# homeboard17.net
KiCad netlist of a schematic drawn in EAGLE
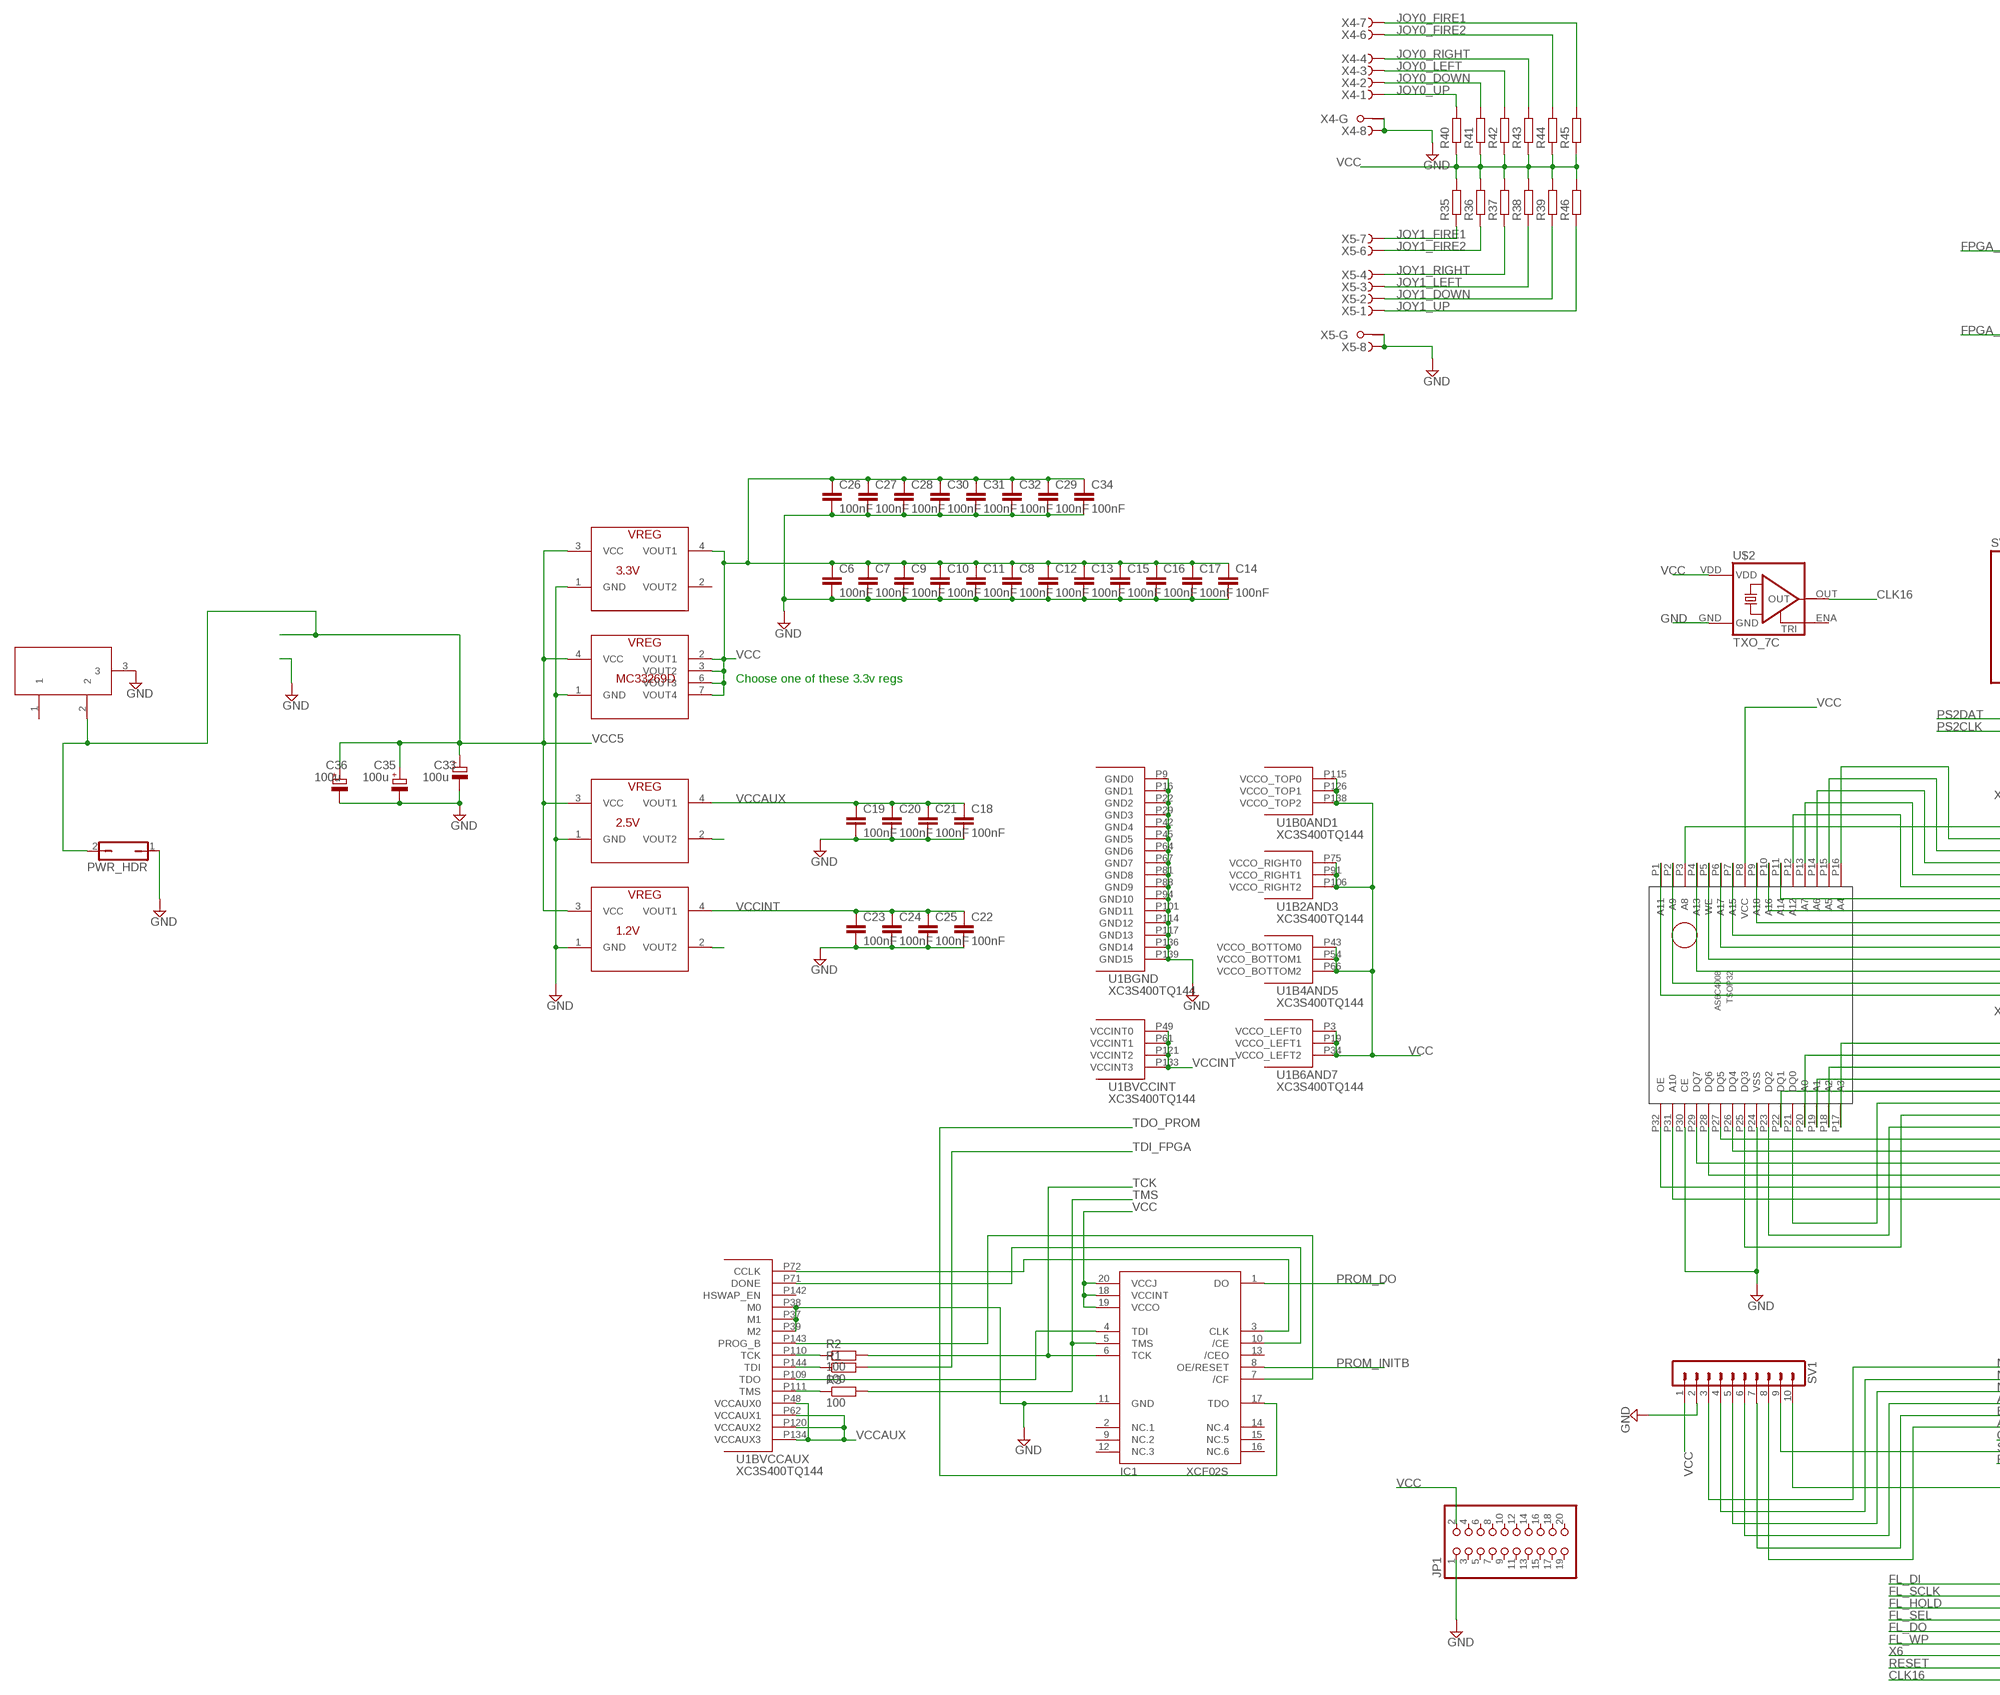
[diagram p0: schematic, sheet 1, part 1 of 3]
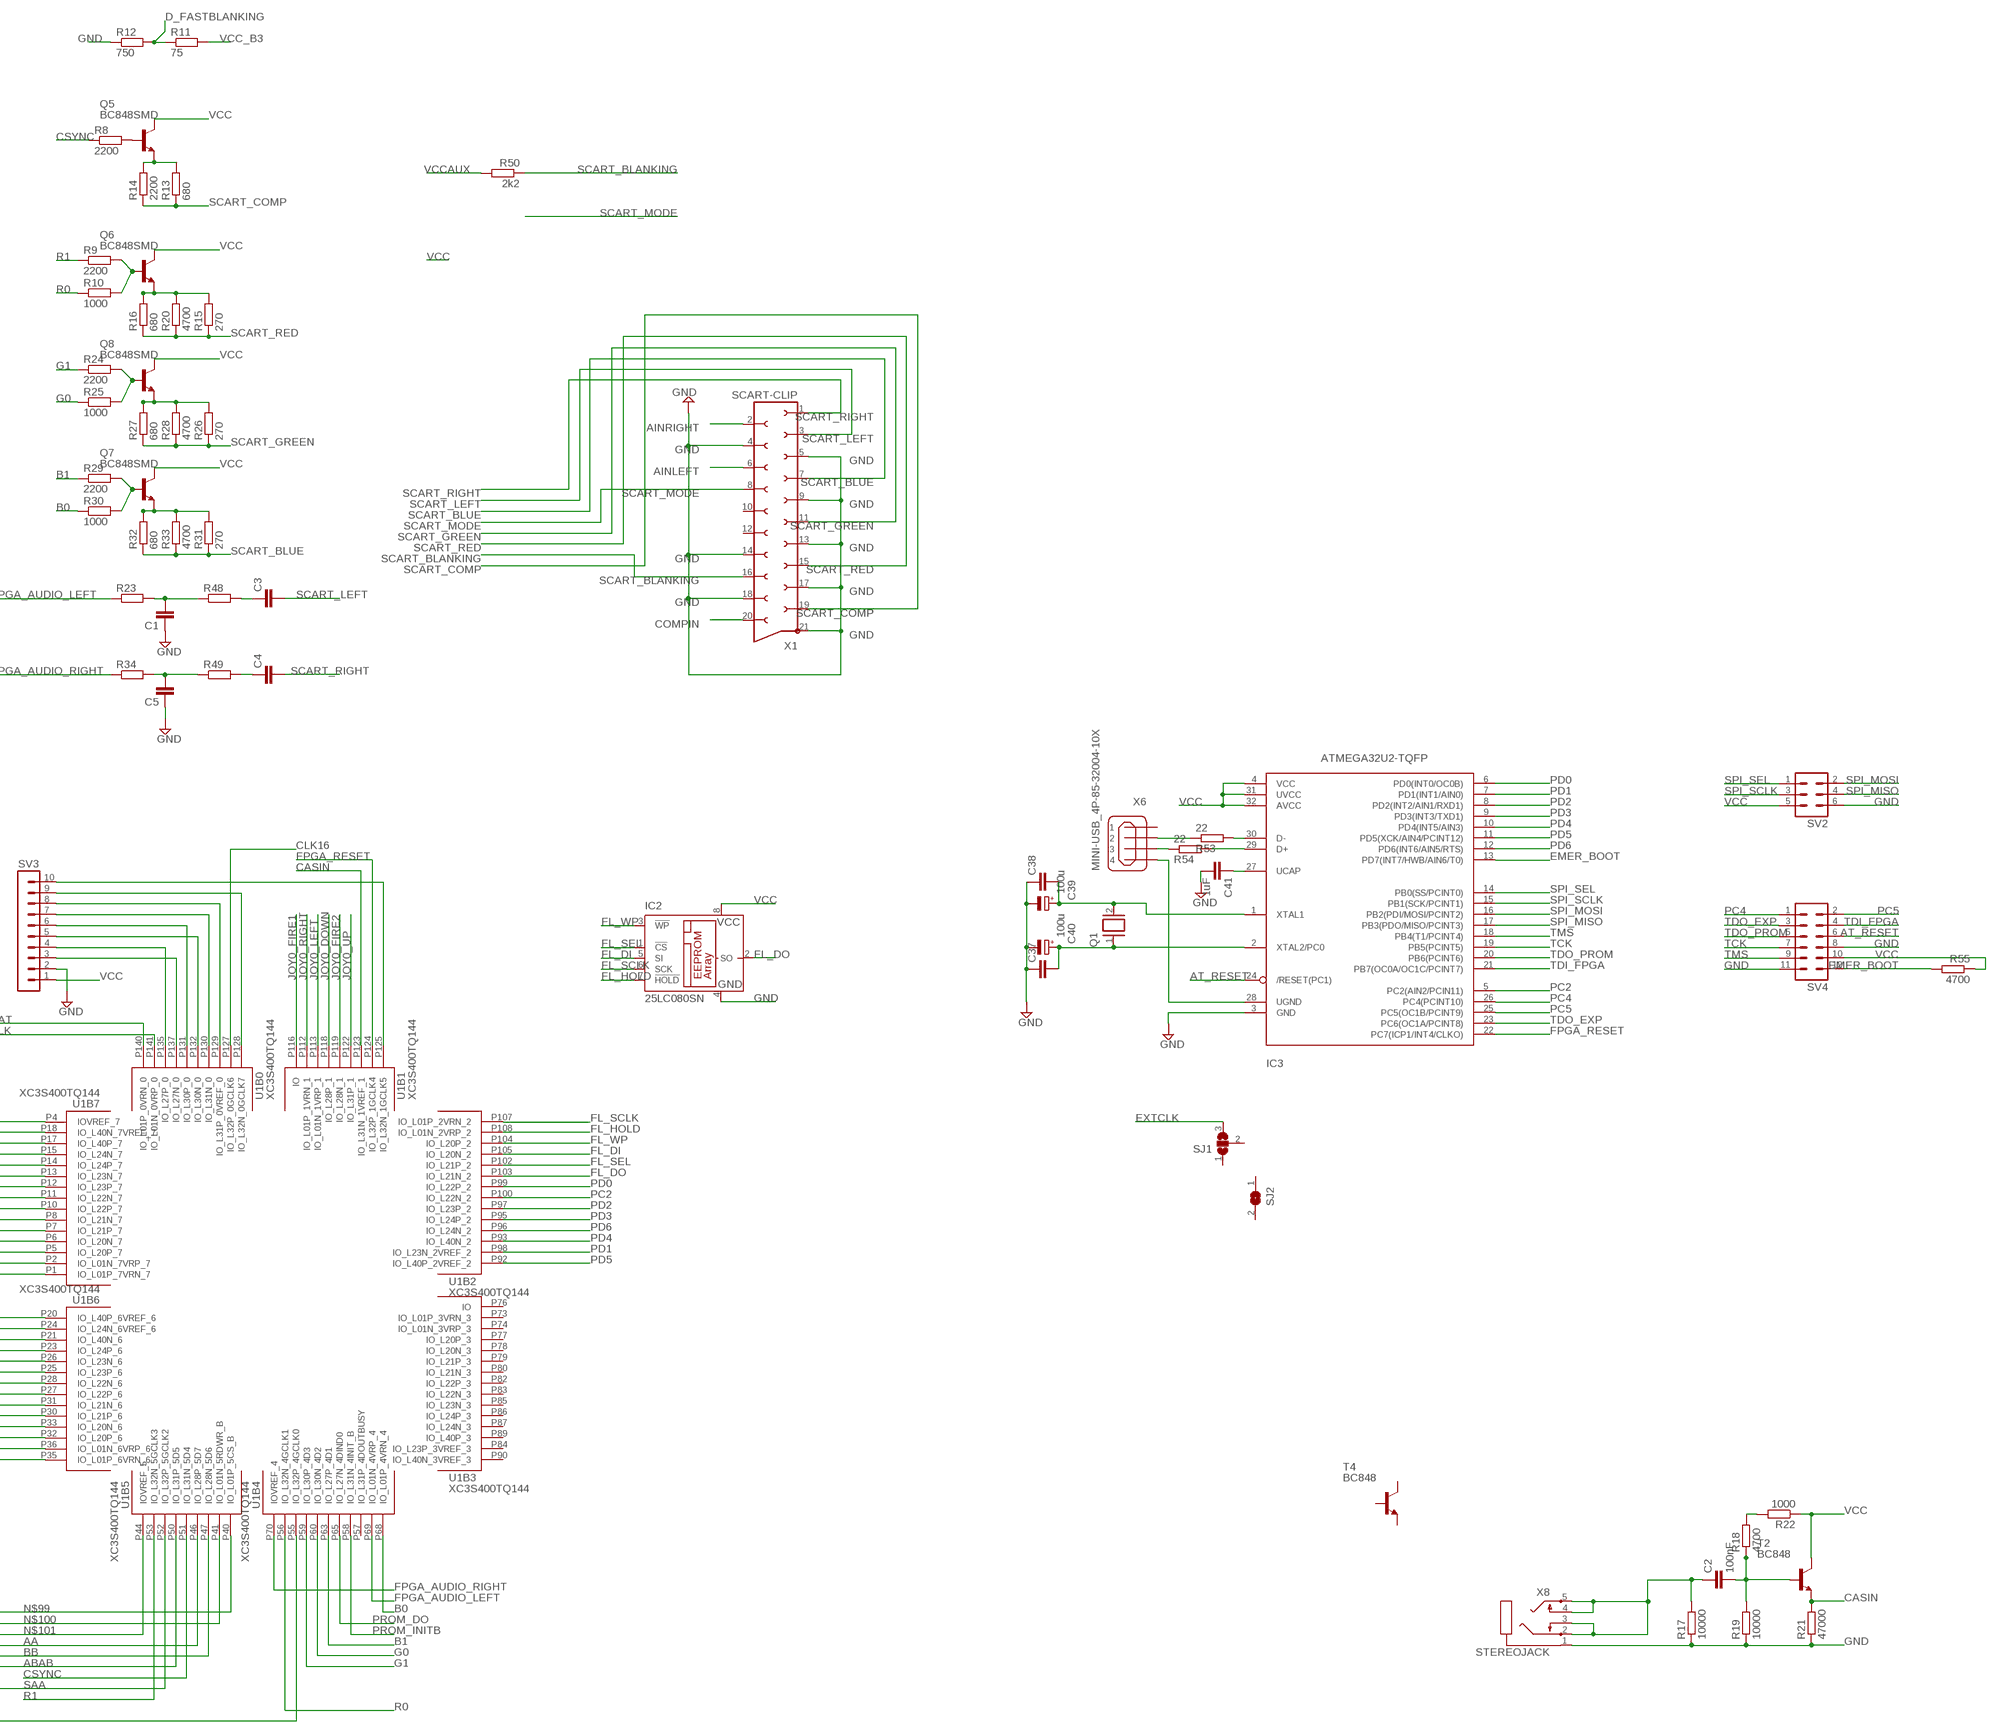
[diagram p1: schematic, sheet 1, part 2 of 3]
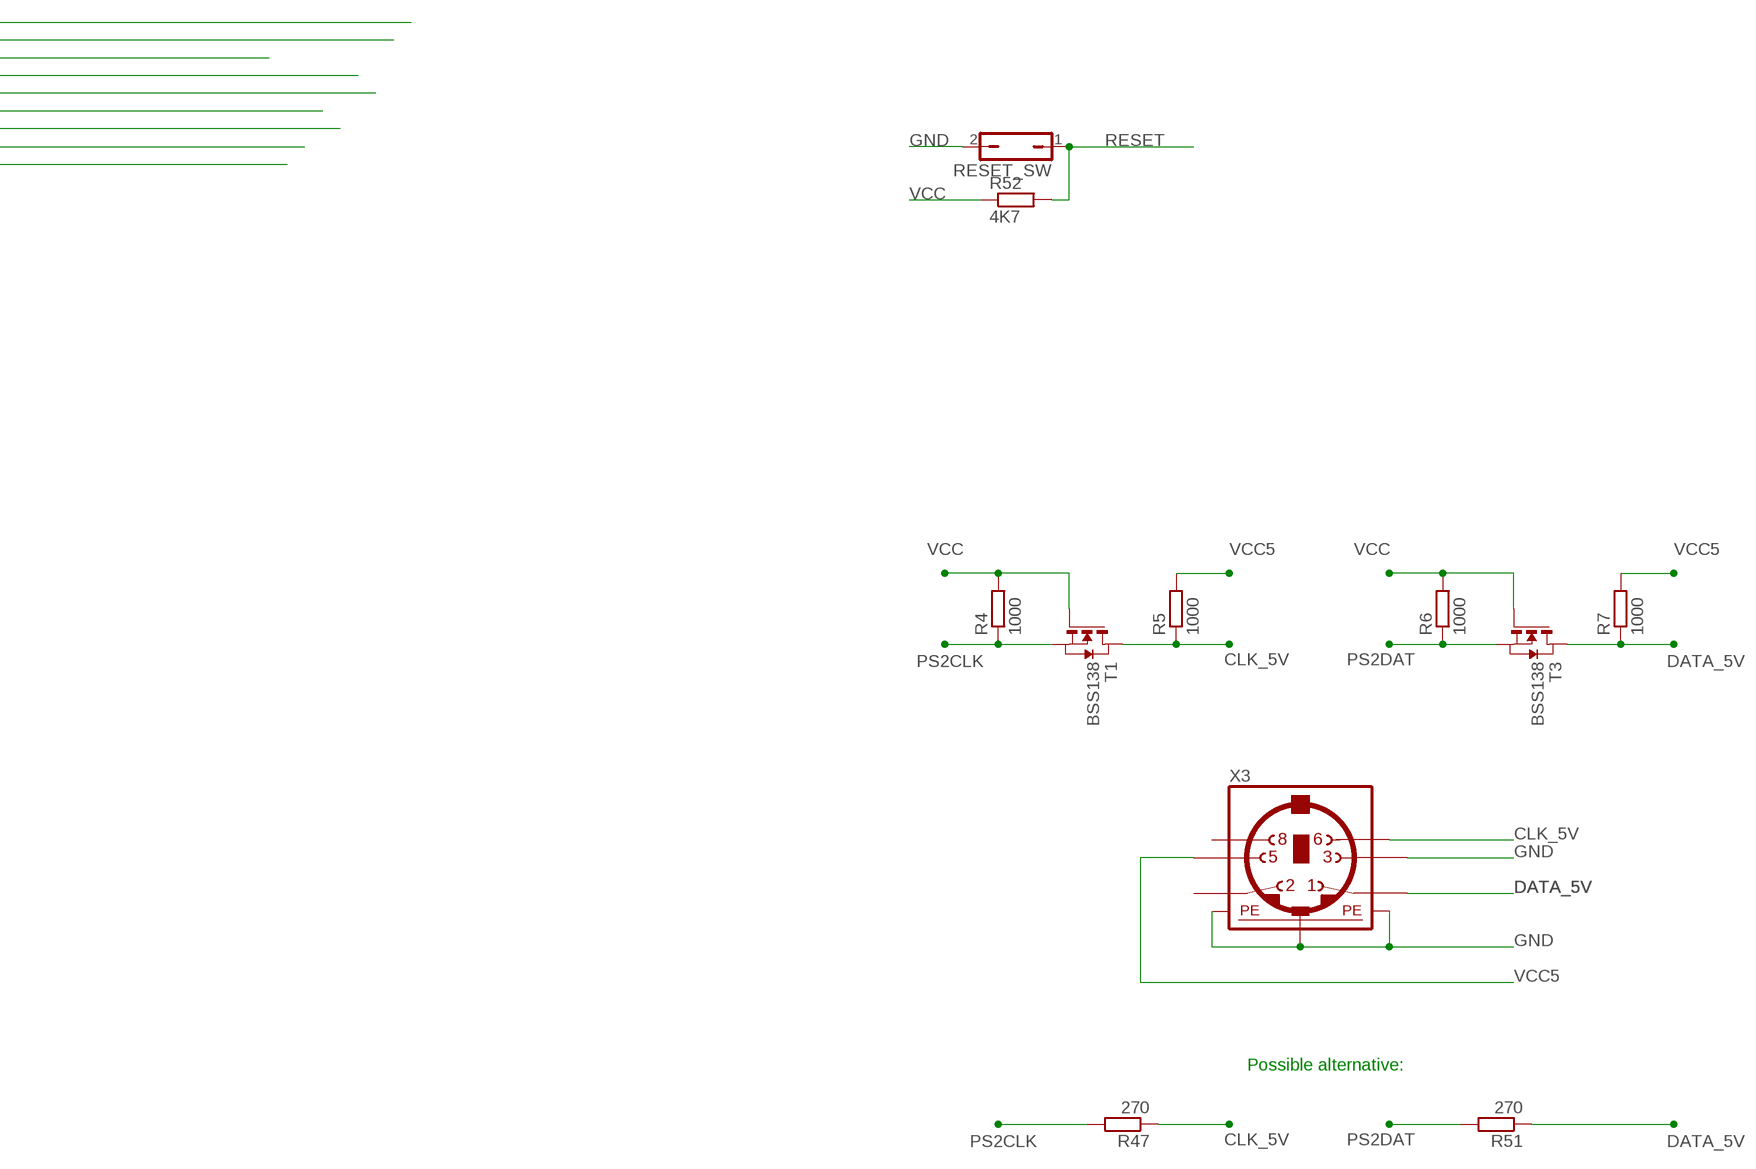
[diagram p2: schematic, sheet 1, part 3 of 3]

(export (version "E")
  (design (tool "Eeschema 10.0.6"))
  (components
    (comp (ref "C1")
      (value "C-EUC0603")
      (footprint "eagle-import:C0603")
      (libsource (lib "eagle-import") (part "resistor_C-EUC0603"))
    )
    (comp (ref "C2")
      (value "100nF")
      (footprint "eagle-import:C0603")
      (libsource (lib "eagle-import") (part "resistor_C-EUC0603"))
    )
    (comp (ref "C3")
      (value "C-EUC0603")
      (footprint "eagle-import:C0603")
      (libsource (lib "eagle-import") (part "resistor_C-EUC0603"))
    )
    (comp (ref "C4")
      (value "C-EUC0603")
      (footprint "eagle-import:C0603")
      (libsource (lib "eagle-import") (part "resistor_C-EUC0603"))
    )
    (comp (ref "C5")
      (value "C-EUC0603")
      (footprint "eagle-import:C0603")
      (libsource (lib "eagle-import") (part "resistor_C-EUC0603"))
    )
    (comp (ref "C6")
      (value "100nF")
      (footprint "eagle-import:C0603")
      (libsource (lib "eagle-import") (part "C-EUC0603"))
    )
    (comp (ref "C7")
      (value "100nF")
      (footprint "eagle-import:C0603")
      (libsource (lib "eagle-import") (part "C-EUC0603"))
    )
    (comp (ref "C8")
      (value "100nF")
      (footprint "eagle-import:C0603")
      (libsource (lib "eagle-import") (part "C-EUC0603"))
    )
    (comp (ref "C9")
      (value "100nF")
      (footprint "eagle-import:C0603")
      (libsource (lib "eagle-import") (part "C-EUC0603"))
    )
    (comp (ref "C10")
      (value "100nF")
      (footprint "eagle-import:C0603")
      (libsource (lib "eagle-import") (part "C-EUC0603"))
    )
    (comp (ref "C11")
      (value "100nF")
      (footprint "eagle-import:C0603")
      (libsource (lib "eagle-import") (part "C-EUC0603"))
    )
    (comp (ref "C12")
      (value "100nF")
      (footprint "eagle-import:C0603")
      (libsource (lib "eagle-import") (part "C-EUC0603"))
    )
    (comp (ref "C13")
      (value "100nF")
      (footprint "eagle-import:C0603")
      (libsource (lib "eagle-import") (part "C-EUC0603"))
    )
    (comp (ref "C14")
      (value "100nF")
      (footprint "eagle-import:C0603")
      (libsource (lib "eagle-import") (part "C-EUC0603"))
    )
    (comp (ref "C15")
      (value "100nF")
      (footprint "eagle-import:C0603")
      (libsource (lib "eagle-import") (part "C-EUC0603"))
    )
    (comp (ref "C16")
      (value "100nF")
      (footprint "eagle-import:C0603")
      (libsource (lib "eagle-import") (part "C-EUC0603"))
    )
    (comp (ref "C17")
      (value "100nF")
      (footprint "eagle-import:C0603")
      (libsource (lib "eagle-import") (part "C-EUC0603"))
    )
    (comp (ref "C18")
      (value "100nF")
      (footprint "eagle-import:C0603")
      (libsource (lib "eagle-import") (part "C-EUC0603"))
    )
    (comp (ref "C19")
      (value "100nF")
      (footprint "eagle-import:C0603")
      (libsource (lib "eagle-import") (part "C-EUC0603"))
    )
    (comp (ref "C20")
      (value "100nF")
      (footprint "eagle-import:C0603")
      (libsource (lib "eagle-import") (part "C-EUC0603"))
    )
    (comp (ref "C21")
      (value "100nF")
      (footprint "eagle-import:C0603")
      (libsource (lib "eagle-import") (part "C-EUC0603"))
    )
    (comp (ref "C22")
      (value "100nF")
      (footprint "eagle-import:C0603")
      (libsource (lib "eagle-import") (part "C-EUC0603"))
    )
    (comp (ref "C23")
      (value "100nF")
      (footprint "eagle-import:C0603")
      (libsource (lib "eagle-import") (part "C-EUC0603"))
    )
    (comp (ref "C24")
      (value "100nF")
      (footprint "eagle-import:C0603")
      (libsource (lib "eagle-import") (part "C-EUC0603"))
    )
    (comp (ref "C25")
      (value "100nF")
      (footprint "eagle-import:C0603")
      (libsource (lib "eagle-import") (part "C-EUC0603"))
    )
    (comp (ref "C26")
      (value "100nF")
      (footprint "eagle-import:C0603")
      (libsource (lib "eagle-import") (part "C-EUC0603"))
    )
    (comp (ref "C27")
      (value "100nF")
      (footprint "eagle-import:C0603")
      (libsource (lib "eagle-import") (part "C-EUC0603"))
    )
    (comp (ref "C28")
      (value "100nF")
      (footprint "eagle-import:C0603")
      (libsource (lib "eagle-import") (part "C-EUC0603"))
    )
    (comp (ref "C29")
      (value "100nF")
      (footprint "eagle-import:C0603")
      (libsource (lib "eagle-import") (part "C-EUC0603"))
    )
    (comp (ref "C30")
      (value "100nF")
      (footprint "eagle-import:C0603")
      (libsource (lib "eagle-import") (part "C-EUC0603"))
    )
    (comp (ref "C31")
      (value "100nF")
      (footprint "eagle-import:C0603")
      (libsource (lib "eagle-import") (part "C-EUC0603"))
    )
    (comp (ref "C32")
      (value "100nF")
      (footprint "eagle-import:C0603")
      (libsource (lib "eagle-import") (part "C-EUC0603"))
    )
    (comp (ref "C33")
      (value "100u")
      (footprint "eagle-import:PANASONIC_D")
      (libsource (lib "eagle-import") (part "CPOL-EUD"))
    )
    (comp (ref "C34")
      (value "100nF")
      (footprint "eagle-import:C0603")
      (libsource (lib "eagle-import") (part "C-EUC0603"))
    )
    (comp (ref "C35")
      (value "100u")
      (footprint "eagle-import:PANASONIC_D")
      (libsource (lib "eagle-import") (part "CPOL-EUD"))
    )
    (comp (ref "C36")
      (value "100u")
      (footprint "eagle-import:PANASONIC_D")
      (libsource (lib "eagle-import") (part "CPOL-EUD"))
    )
    (comp (ref "C37")
      (value "C-EUC0805")
      (footprint "eagle-import:C0805")
      (libsource (lib "eagle-import") (part "C-EUC0805"))
    )
    (comp (ref "C38")
      (value "C-EUC0805")
      (footprint "eagle-import:C0805")
      (libsource (lib "eagle-import") (part "C-EUC0805"))
    )
    (comp (ref "C39")
      (value "100u")
      (footprint "eagle-import:PANASONIC_D")
      (libsource (lib "eagle-import") (part "CPOL-EUD"))
    )
    (comp (ref "C40")
      (value "100u")
      (footprint "eagle-import:PANASONIC_D")
      (libsource (lib "eagle-import") (part "CPOL-EUD"))
    )
    (comp (ref "C41")
      (value "1uF")
      (footprint "eagle-import:C0805")
      (libsource (lib "eagle-import") (part "C-EUC0805"))
    )
    (comp (ref "IC1")
      (value "XCF02S")
      (footprint "eagle-import:VO20")
      (libsource (lib "eagle-import") (part "XCF02S"))
    )
    (comp (ref "IC2")
      (value "25LC080SN")
      (footprint "eagle-import:SO-08")
      (fields (field (name "MF") "MICROCHIP") (field (name "MPN") "25LC080/SN"))
      (libsource (lib "eagle-import") (part "25SNLC080"))
    )
    (comp (ref "IC3")
      (value "ATMEGA32U2-TQFP")
      (footprint "eagle-import:TQFP32-08")
      (libsource (lib "eagle-import") (part "ATMEGA32U2-TQFP"))
    )
    (comp (ref "JP1")
      (value "PINHD-2X10")
      (footprint "eagle-import:2X10")
      (libsource (lib "eagle-import") (part "PINHD-2X10"))
    )
    (comp (ref "PWR_HDR")
      (value "JP1Q")
      (footprint "eagle-import:JP1")
      (libsource (lib "eagle-import") (part "JP1Q"))
    )
    (comp (ref "Q1")
      (value "XTAL/S")
      (footprint "eagle-import:QS")
      (libsource (lib "eagle-import") (part "XTAL/S"))
    )
    (comp (ref "Q5")
      (value "BC848SMD")
      (footprint "eagle-import:SOT23")
      (libsource (lib "eagle-import") (part "BC848SMD"))
    )
    (comp (ref "Q6")
      (value "BC848SMD")
      (footprint "eagle-import:SOT23")
      (libsource (lib "eagle-import") (part "BC848SMD"))
    )
    (comp (ref "Q7")
      (value "BC848SMD")
      (footprint "eagle-import:SOT23")
      (libsource (lib "eagle-import") (part "BC848SMD"))
    )
    (comp (ref "Q8")
      (value "BC848SMD")
      (footprint "eagle-import:SOT23")
      (libsource (lib "eagle-import") (part "BC848SMD"))
    )
    (comp (ref "R1")
      (value "100")
      (footprint "eagle-import:R0805")
      (libsource (lib "eagle-import") (part "R-EU_R0805"))
    )
    (comp (ref "R2")
      (value "100")
      (footprint "eagle-import:R0805")
      (libsource (lib "eagle-import") (part "R-EU_R0805"))
    )
    (comp (ref "R3")
      (value "100")
      (footprint "eagle-import:R0805")
      (libsource (lib "eagle-import") (part "R-EU_R0805"))
    )
    (comp (ref "R4")
      (value "1000")
      (footprint "eagle-import:R0805")
      (libsource (lib "eagle-import") (part "R-EU_R0805"))
    )
    (comp (ref "R5")
      (value "1000")
      (footprint "eagle-import:R0805")
      (libsource (lib "eagle-import") (part "R-EU_R0805"))
    )
    (comp (ref "R6")
      (value "1000")
      (footprint "eagle-import:R0805")
      (libsource (lib "eagle-import") (part "R-EU_R0805"))
    )
    (comp (ref "R7")
      (value "1000")
      (footprint "eagle-import:R0805")
      (libsource (lib "eagle-import") (part "R-EU_R0805"))
    )
    (comp (ref "R8")
      (value "2200")
      (footprint "eagle-import:R0805")
      (libsource (lib "eagle-import") (part "R-EU_R0805"))
    )
    (comp (ref "R9")
      (value "2200")
      (footprint "eagle-import:R0805")
      (libsource (lib "eagle-import") (part "R-EU_R0805"))
    )
    (comp (ref "R10")
      (value "1000")
      (footprint "eagle-import:R0805")
      (libsource (lib "eagle-import") (part "R-EU_R0805"))
    )
    (comp (ref "R11")
      (value "75")
      (footprint "eagle-import:R0805")
      (libsource (lib "eagle-import") (part "R-EU_R0805"))
    )
    (comp (ref "R12")
      (value "750")
      (footprint "eagle-import:R0805")
      (libsource (lib "eagle-import") (part "R-EU_R0805"))
    )
    (comp (ref "R13")
      (value "680")
      (footprint "eagle-import:R0805")
      (libsource (lib "eagle-import") (part "R-EU_R0805"))
    )
    (comp (ref "R14")
      (value "2200")
      (footprint "eagle-import:R0805")
      (libsource (lib "eagle-import") (part "R-EU_R0805"))
    )
    (comp (ref "R15")
      (value "270")
      (footprint "eagle-import:R0805")
      (libsource (lib "eagle-import") (part "R-EU_R0805"))
    )
    (comp (ref "R16")
      (value "680")
      (footprint "eagle-import:R0805")
      (libsource (lib "eagle-import") (part "R-EU_R0805"))
    )
    (comp (ref "R17")
      (value "10000")
      (footprint "eagle-import:R0805")
      (libsource (lib "eagle-import") (part "R-EU_R0805"))
    )
    (comp (ref "R18")
      (value "4700")
      (footprint "eagle-import:R0805")
      (libsource (lib "eagle-import") (part "R-EU_R0805"))
    )
    (comp (ref "R19")
      (value "10000")
      (footprint "eagle-import:R0805")
      (libsource (lib "eagle-import") (part "R-EU_R0805"))
    )
    (comp (ref "R20")
      (value "4700")
      (footprint "eagle-import:R0805")
      (libsource (lib "eagle-import") (part "R-EU_R0805"))
    )
    (comp (ref "R21")
      (value "47000")
      (footprint "eagle-import:R0805")
      (libsource (lib "eagle-import") (part "R-EU_R0805"))
    )
    (comp (ref "R22")
      (value "1000")
      (footprint "eagle-import:R0805")
      (libsource (lib "eagle-import") (part "R-EU_R0805"))
    )
    (comp (ref "R23")
      (value "R-EU_M0805")
      (footprint "eagle-import:M0805")
      (libsource (lib "eagle-import") (part "resistor_R-EU_M0805"))
    )
    (comp (ref "R24")
      (value "2200")
      (footprint "eagle-import:R0805")
      (libsource (lib "eagle-import") (part "R-EU_R0805"))
    )
    (comp (ref "R25")
      (value "1000")
      (footprint "eagle-import:R0805")
      (libsource (lib "eagle-import") (part "R-EU_R0805"))
    )
    (comp (ref "R26")
      (value "270")
      (footprint "eagle-import:R0805")
      (libsource (lib "eagle-import") (part "R-EU_R0805"))
    )
    (comp (ref "R27")
      (value "680")
      (footprint "eagle-import:R0805")
      (libsource (lib "eagle-import") (part "R-EU_R0805"))
    )
    (comp (ref "R28")
      (value "4700")
      (footprint "eagle-import:R0805")
      (libsource (lib "eagle-import") (part "R-EU_R0805"))
    )
    (comp (ref "R29")
      (value "2200")
      (footprint "eagle-import:R0805")
      (libsource (lib "eagle-import") (part "R-EU_R0805"))
    )
    (comp (ref "R30")
      (value "1000")
      (footprint "eagle-import:R0805")
      (libsource (lib "eagle-import") (part "R-EU_R0805"))
    )
    (comp (ref "R31")
      (value "270")
      (footprint "eagle-import:R0805")
      (libsource (lib "eagle-import") (part "R-EU_R0805"))
    )
    (comp (ref "R32")
      (value "680")
      (footprint "eagle-import:R0805")
      (libsource (lib "eagle-import") (part "R-EU_R0805"))
    )
    (comp (ref "R33")
      (value "4700")
      (footprint "eagle-import:R0805")
      (libsource (lib "eagle-import") (part "R-EU_R0805"))
    )
    (comp (ref "R34")
      (value "R-EU_M0805")
      (footprint "eagle-import:M0805")
      (libsource (lib "eagle-import") (part "resistor_R-EU_M0805"))
    )
    (comp (ref "R35")
      (value "R-EU_M0805")
      (footprint "eagle-import:M0805")
      (libsource (lib "eagle-import") (part "resistor_R-EU_M0805"))
    )
    (comp (ref "R36")
      (value "R-EU_M0805")
      (footprint "eagle-import:M0805")
      (libsource (lib "eagle-import") (part "resistor_R-EU_M0805"))
    )
    (comp (ref "R37")
      (value "R-EU_M0805")
      (footprint "eagle-import:M0805")
      (libsource (lib "eagle-import") (part "resistor_R-EU_M0805"))
    )
    (comp (ref "R38")
      (value "R-EU_M0805")
      (footprint "eagle-import:M0805")
      (libsource (lib "eagle-import") (part "resistor_R-EU_M0805"))
    )
    (comp (ref "R39")
      (value "R-EU_M0805")
      (footprint "eagle-import:M0805")
      (libsource (lib "eagle-import") (part "resistor_R-EU_M0805"))
    )
    (comp (ref "R40")
      (value "R-EU_M0805")
      (footprint "eagle-import:M0805")
      (libsource (lib "eagle-import") (part "resistor_R-EU_M0805"))
    )
    (comp (ref "R41")
      (value "R-EU_M0805")
      (footprint "eagle-import:M0805")
      (libsource (lib "eagle-import") (part "resistor_R-EU_M0805"))
    )
    (comp (ref "R42")
      (value "R-EU_M0805")
      (footprint "eagle-import:M0805")
      (libsource (lib "eagle-import") (part "resistor_R-EU_M0805"))
    )
    (comp (ref "R43")
      (value "R-EU_M0805")
      (footprint "eagle-import:M0805")
      (libsource (lib "eagle-import") (part "resistor_R-EU_M0805"))
    )
    (comp (ref "R44")
      (value "R-EU_M0805")
      (footprint "eagle-import:M0805")
      (libsource (lib "eagle-import") (part "resistor_R-EU_M0805"))
    )
    (comp (ref "R45")
      (value "R-EU_M0805")
      (footprint "eagle-import:M0805")
      (libsource (lib "eagle-import") (part "resistor_R-EU_M0805"))
    )
    (comp (ref "R46")
      (value "R-EU_M0805")
      (footprint "eagle-import:M0805")
      (libsource (lib "eagle-import") (part "resistor_R-EU_M0805"))
    )
    (comp (ref "R47")
      (value "270")
      (footprint "eagle-import:R0805")
      (libsource (lib "eagle-import") (part "R-EU_R0805"))
    )
    (comp (ref "R48")
      (value "R-EU_M0805")
      (footprint "eagle-import:M0805")
      (libsource (lib "eagle-import") (part "resistor_R-EU_M0805"))
    )
    (comp (ref "R49")
      (value "R-EU_M0805")
      (footprint "eagle-import:M0805")
      (libsource (lib "eagle-import") (part "resistor_R-EU_M0805"))
    )
    (comp (ref "R50")
      (value "2k2")
      (footprint "eagle-import:M0805")
      (libsource (lib "eagle-import") (part "resistor_R-EU_M0805"))
    )
    (comp (ref "R51")
      (value "270")
      (footprint "eagle-import:R0805")
      (libsource (lib "eagle-import") (part "R-EU_R0805"))
    )
    (comp (ref "R52")
      (value "4K7")
      (footprint "eagle-import:M0805")
      (libsource (lib "eagle-import") (part "resistor_R-EU_M0805"))
    )
    (comp (ref "R53")
      (value "22")
      (footprint "eagle-import:R0805")
      (libsource (lib "eagle-import") (part "R-EU_R0805"))
    )
    (comp (ref "R54")
      (value "22")
      (footprint "eagle-import:R0805")
      (libsource (lib "eagle-import") (part "R-EU_R0805"))
    )
    (comp (ref "R55")
      (value "4700")
      (footprint "eagle-import:R0805")
      (libsource (lib "eagle-import") (part "R-EU_R0805"))
    )
    (comp (ref "REG1.2")
      (value "1.2V")
      (footprint "eagle-import:SOT223")
      (libsource (lib "eagle-import") (part "NX1117"))
    )
    (comp (ref "REG2.5")
      (value "2.5V")
      (footprint "eagle-import:SOT223")
      (libsource (lib "eagle-import") (part "NX1117"))
    )
    (comp (ref "RESET_SW")
      (value "JP1Q")
      (footprint "eagle-import:JP1")
      (libsource (lib "eagle-import") (part "JP1Q"))
    )
    (comp (ref "SJ1")
      (value "SJ2W")
      (footprint "eagle-import:SJ_2")
      (libsource (lib "eagle-import") (part "SJ2W"))
    )
    (comp (ref "SJ2") (value "SJ") (footprint "eagle-import:SJ") (libsource (lib "eagle-import") (part "SJ")))
    (comp (ref "SV1")
      (value "MA10-1")
      (footprint "eagle-import:MA10-1")
      (fields (field (name "OC_FARNELL") "unknown") (field (name "OC_NEWARK") "unknown"))
      (libsource (lib "eagle-import") (part "MA10-1"))
    )
    (comp (ref "SV2")
      (value "MA03-2")
      (footprint "eagle-import:MA03-2")
      (libsource (lib "eagle-import") (part "MA03-2"))
    )
    (comp (ref "SV3")
      (value "MA10-1")
      (footprint "eagle-import:MA10-1")
      (libsource (lib "eagle-import") (part "MA10-1"))
    )
    (comp (ref "SV4")
      (value "MA06-2")
      (footprint "eagle-import:MA06-2")
      (libsource (lib "eagle-import") (part "MA06-2"))
    )
    (comp (ref "T1")
      (value "BSS138")
      (footprint "eagle-import:SOT-23")
      (libsource (lib "eagle-import") (part "NMOSSOT23"))
    )
    (comp (ref "T2")
      (value "BC848")
      (footprint "eagle-import:SOT23")
      (libsource (lib "eagle-import") (part "BC848"))
    )
    (comp (ref "T3")
      (value "BSS138")
      (footprint "eagle-import:SOT-23")
      (libsource (lib "eagle-import") (part "NMOSSOT23"))
    )
    (comp (ref "T4")
      (value "BC848")
      (footprint "eagle-import:SOT23")
      (libsource (lib "eagle-import") (part "BC848"))
    )
    (comp (ref "U$2")
      (value "TXO_7C")
      (footprint "eagle-import:OSC_7C")
      (libsource (lib "eagle-import") (part "TXO_7C"))
    )
    (comp (ref "U$4")
      (value "3.3V")
      (footprint "eagle-import:SOT223")
      (libsource (lib "eagle-import") (part "NX1117"))
    )
    (comp (ref "U$5")
      (value "MC33269D")
      (footprint "eagle-import:SO8")
      (libsource (lib "eagle-import") (part "MC33269D"))
    )
    (comp (ref "U$6")
      (value "AS6C4008")
      (footprint "eagle-import:TSOP32")
      (libsource (lib "eagle-import") (part "AS6C4008"))
    )
    (comp (ref "U1")
      (value "XC3S400TQ144")
      (footprint "eagle-import:TQ144")
      (libsource (lib "eagle-import") (part "XC3S400TQ144"))
    )
    (comp (ref "X1")
      (value "SCART-CLIP")
      (footprint "eagle-import:SCART-CLIP")
      (libsource (lib "eagle-import") (part "SCART-CLIP"))
    )
    (comp (ref "X3")
      (value "MINI_DIN_6")
      (footprint "eagle-import:M_DIN6")
      (libsource (lib "eagle-import") (part "MINI_DIN_6"))
    )
    (comp (ref "X4")
      (value "F09HPS")
      (footprint "eagle-import:F09HP")
      (libsource (lib "eagle-import") (part "F09HPS"))
    )
    (comp (ref "X5")
      (value "F09HPS")
      (footprint "eagle-import:F09HP")
      (libsource (lib "eagle-import") (part "F09HPS"))
    )
    (comp (ref "X6")
      (value "MINI-USB_4P-85-32004-10X")
      (footprint "eagle-import:85-32004-10X")
      (libsource (lib "eagle-import") (part "MINI-USB_4P-85-32004-10X"))
    )
    (comp (ref "X7")
      (value "DC21MMX")
      (footprint "eagle-import:DC-21MM")
      (libsource (lib "eagle-import") (part "DC21MMX"))
    )
    (comp (ref "X8")
      (value "STEREOJACK")
      (footprint "eagle-import:20-0137")
      (libsource (lib "eagle-import") (part "STEREOJACK"))
    )
  )
  (nets
    (net (code "1") (name "/1") (class "Default")
      (node (ref "X7") (pin "1") (pinfunction "1_1") (pintype "power_in"))
    )
    (net (code "2") (name "/AA") (class "Default")
      (node (ref "SV1") (pin "6") (pinfunction "6_6") (pintype "passive"))
      (node (ref "U1") (pin "P46") (pinfunction "IO_L28P_5D7_P46") (pintype "bidirectional"))
    )
    (net (code "3") (name "/ABAB") (class "Default")
      (node (ref "SV1") (pin "8") (pinfunction "8_8") (pintype "passive"))
      (node (ref "U1") (pin "P50") (pinfunction "IO_L31P_5D5_P50") (pintype "bidirectional"))
    )
    (net (code "4") (name "/AINLEFT") (class "Default")
      (node (ref "X1") (pin "6") (pinfunction "6_6") (pintype "passive"))
    )
    (net (code "5") (name "/AINRIGHT") (class "Default")
      (node (ref "X1") (pin "2") (pinfunction "2_2") (pintype "passive"))
    )
    (net (code "6") (name "/AT_RESET") (class "Default")
      (node (ref "IC3") (pin "24") (pinfunction "/RESET(PC1)_24") (pintype "bidirectional"))
      (node (ref "SV4") (pin "6") (pinfunction "6_6") (pintype "passive"))
    )
    (net (code "7") (name "/B0") (class "Default")
      (node (ref "R30") (pin "1") (pinfunction "1_1") (pintype "passive"))
      (node (ref "U1") (pin "P68") (pinfunction "IO_L01P_4VRN_4_P68") (pintype "bidirectional"))
    )
    (net (code "8") (name "/B1") (class "Default")
      (node (ref "R29") (pin "1") (pinfunction "1_1") (pintype "passive"))
      (node (ref "U1") (pin "P63") (pinfunction "IO_L27P_4D1_P63") (pintype "bidirectional"))
    )
    (net (code "9") (name "/BB") (class "Default")
      (node (ref "SV1") (pin "7") (pinfunction "7_7") (pintype "passive"))
      (node (ref "U1") (pin "P47") (pinfunction "IO_L28N_5D6_P47") (pintype "bidirectional"))
    )
    (net (code "10") (name "/CASIN") (class "Default")
      (node (ref "R21") (pin "2") (pinfunction "2_2") (pintype "passive"))
      (node (ref "T2") (pin "2") (pinfunction "E_2") (pintype "passive"))
      (node (ref "U1") (pin "P123") (pinfunction "IO_L31N_1VREF_1_P123") (pintype "bidirectional"))
    )
    (net (code "11") (name "/CLK16") (class "Default")
      (node (ref "U$2") (pin "OUT") (pinfunction "OUT_OUT") (pintype "output"))
      (node (ref "U1") (pin "P127") (pinfunction "IO_L32P_0GCLK6_P127") (pintype "bidirectional"))
    )
    (net (code "12") (name "/CLK_5V") (class "Default")
      (node (ref "R47") (pin "1") (pinfunction "1_1") (pintype "passive"))
      (node (ref "R5") (pin "1") (pinfunction "1_1") (pintype "passive"))
      (node (ref "T1") (pin "1") (pinfunction "D_1") (pintype "passive"))
      (node (ref "X3") (pin "6") (pinfunction "6_6") (pintype "passive"))
    )
    (net (code "13") (name "/COMPIN") (class "Default")
      (node (ref "X1") (pin "20") (pinfunction "20_20") (pintype "passive"))
    )
    (net (code "14") (name "/CSYNC") (class "Default")
      (node (ref "R8") (pin "1") (pinfunction "1_1") (pintype "passive"))
      (node (ref "U1") (pin "P51") (pinfunction "IO_L31N_5D4_P51") (pintype "bidirectional"))
    )
    (net (code "15") (name "/DATA_5V") (class "Default")
      (node (ref "R51") (pin "1") (pinfunction "1_1") (pintype "passive"))
      (node (ref "R7") (pin "1") (pinfunction "1_1") (pintype "passive"))
      (node (ref "T3") (pin "1") (pinfunction "D_1") (pintype "passive"))
      (node (ref "X3") (pin "1") (pinfunction "1_1") (pintype "passive"))
    )
    (net (code "16") (name "/D_FASTBLANKING") (class "Default")
      (node (ref "R11") (pin "1") (pinfunction "1_1") (pintype "passive"))
      (node (ref "R12") (pin "2") (pinfunction "2_2") (pintype "passive"))
    )
    (net (code "17") (name "/EMER_BOOT") (class "Default")
      (node (ref "IC3") (pin "13") (pinfunction "PD7(INT7/HWB/AIN6/T0)_13") (pintype "bidirectional"))
      (node (ref "R55") (pin "2") (pinfunction "2_2") (pintype "passive"))
      (node (ref "SV4") (pin "12") (pinfunction "12_12") (pintype "passive"))
    )
    (net (code "18") (name "/EXTCLK") (class "Default")
      (node (ref "SJ1") (pin "3") (pinfunction "3_3") (pintype "passive"))
    )
    (net (code "19") (name "/FL_DI") (class "Default")
      (node (ref "IC2") (pin "5") (pinfunction "SI_5") (pintype "input"))
      (node (ref "U1") (pin "P105") (pinfunction "IO_L20N_2_P105") (pintype "bidirectional"))
    )
    (net (code "20") (name "/FL_DO") (class "Default")
      (node (ref "IC2") (pin "2") (pinfunction "SO_2") (pintype "bidirectional"))
      (node (ref "U1") (pin "P103") (pinfunction "IO_L21N_2_P103") (pintype "bidirectional"))
    )
    (net (code "21") (name "/FL_HOLD") (class "Default")
      (node (ref "IC2") (pin "7") (pinfunction "~{HOLD}_7") (pintype "input"))
      (node (ref "U1") (pin "P108") (pinfunction "IO_L01N_2VRP_2_P108") (pintype "bidirectional"))
    )
    (net (code "22") (name "/FL_SCLK") (class "Default")
      (node (ref "IC2") (pin "6") (pinfunction "SCK_6") (pintype "input"))
      (node (ref "U1") (pin "P107") (pinfunction "IO_L01P_2VRN_2_P107") (pintype "bidirectional"))
    )
    (net (code "23") (name "/FL_SEL") (class "Default")
      (node (ref "IC2") (pin "1") (pinfunction "~{CS}_1") (pintype "input"))
      (node (ref "U1") (pin "P102") (pinfunction "IO_L21P_2_P102") (pintype "bidirectional"))
    )
    (net (code "24") (name "/FL_WP") (class "Default")
      (node (ref "IC2") (pin "3") (pinfunction "~{WP}_3") (pintype "input"))
      (node (ref "U1") (pin "P104") (pinfunction "IO_L20P_2_P104") (pintype "bidirectional"))
    )
    (net (code "25") (name "/FPGA_AUDIO_LEFT") (class "Default")
      (node (ref "R23") (pin "1") (pinfunction "1_1") (pintype "passive"))
      (node (ref "U1") (pin "P69") (pinfunction "IO_L01N_4VRP_4_P69") (pintype "bidirectional"))
    )
    (net (code "26") (name "/FPGA_AUDIO_RIGHT") (class "Default")
      (node (ref "R34") (pin "1") (pinfunction "1_1") (pintype "passive"))
      (node (ref "U1") (pin "P70") (pinfunction "IOVREF_4_P70") (pintype "bidirectional"))
    )
    (net (code "27") (name "/FPGA_RESET") (class "Default")
      (node (ref "IC3") (pin "22") (pinfunction "PC7(ICP1/INT4/CLKO)_22") (pintype "bidirectional"))
      (node (ref "U1") (pin "P124") (pinfunction "IO_L32P_1GCLK4_P124") (pintype "bidirectional"))
    )
    (net (code "28") (name "/G0") (class "Default")
      (node (ref "R25") (pin "1") (pinfunction "1_1") (pintype "passive"))
      (node (ref "U1") (pin "P60") (pinfunction "IO_L30N_4D2_P60") (pintype "bidirectional"))
    )
    (net (code "29") (name "/G1") (class "Default")
      (node (ref "R24") (pin "1") (pinfunction "1_1") (pintype "passive"))
      (node (ref "U1") (pin "P59") (pinfunction "IO_L30P_4D3_P59") (pintype "bidirectional"))
    )
    (net (code "30") (name "/JOY0_DOWN") (class "Default")
      (node (ref "R41") (pin "2") (pinfunction "2_2") (pintype "passive"))
      (node (ref "U1") (pin "P118") (pinfunction "IO_L28P_1_P118") (pintype "bidirectional"))
      (node (ref "X4") (pin "2") (pinfunction "F_2") (pintype "passive"))
    )
    (net (code "31") (name "/JOY0_FIRE1") (class "Default")
      (node (ref "R45") (pin "2") (pinfunction "2_2") (pintype "passive"))
      (node (ref "U1") (pin "P116") (pinfunction "IO_P116") (pintype "bidirectional"))
      (node (ref "X4") (pin "7") (pinfunction "F_7") (pintype "passive"))
    )
    (net (code "32") (name "/JOY0_FIRE2") (class "Default")
      (node (ref "R44") (pin "2") (pinfunction "2_2") (pintype "passive"))
      (node (ref "U1") (pin "P119") (pinfunction "IO_L28N_1_P119") (pintype "bidirectional"))
      (node (ref "X4") (pin "6") (pinfunction "F_6") (pintype "passive"))
    )
    (net (code "33") (name "/JOY0_LEFT") (class "Default")
      (node (ref "R42") (pin "2") (pinfunction "2_2") (pintype "passive"))
      (node (ref "U1") (pin "P113") (pinfunction "IO_L01N_1VRP_1_P113") (pintype "bidirectional"))
      (node (ref "X4") (pin "3") (pinfunction "F_3") (pintype "passive"))
    )
    (net (code "34") (name "/JOY0_RIGHT") (class "Default")
      (node (ref "R43") (pin "2") (pinfunction "2_2") (pintype "passive"))
      (node (ref "U1") (pin "P112") (pinfunction "IO_L01P_1VRN_1_P112") (pintype "bidirectional"))
      (node (ref "X4") (pin "4") (pinfunction "F_4") (pintype "passive"))
    )
    (net (code "35") (name "/JOY0_UP") (class "Default")
      (node (ref "R40") (pin "2") (pinfunction "2_2") (pintype "passive"))
      (node (ref "U1") (pin "P122") (pinfunction "IO_L31P_1_P122") (pintype "bidirectional"))
      (node (ref "X4") (pin "1") (pinfunction "F_1") (pintype "passive"))
    )
    (net (code "36") (name "/JOY1_DOWN") (class "Default")
      (node (ref "R39") (pin "1") (pinfunction "1_1") (pintype "passive"))
      (node (ref "X5") (pin "2") (pinfunction "F_2") (pintype "passive"))
    )
    (net (code "37") (name "/JOY1_FIRE1") (class "Default")
      (node (ref "R35") (pin "1") (pinfunction "1_1") (pintype "passive"))
      (node (ref "X5") (pin "7") (pinfunction "F_7") (pintype "passive"))
    )
    (net (code "38") (name "/JOY1_FIRE2") (class "Default")
      (node (ref "R36") (pin "1") (pinfunction "1_1") (pintype "passive"))
      (node (ref "X5") (pin "6") (pinfunction "F_6") (pintype "passive"))
    )
    (net (code "39") (name "/JOY1_LEFT") (class "Default")
      (node (ref "R38") (pin "1") (pinfunction "1_1") (pintype "passive"))
      (node (ref "X5") (pin "3") (pinfunction "F_3") (pintype "passive"))
    )
    (net (code "40") (name "/JOY1_RIGHT") (class "Default")
      (node (ref "R37") (pin "1") (pinfunction "1_1") (pintype "passive"))
      (node (ref "X5") (pin "4") (pinfunction "F_4") (pintype "passive"))
    )
    (net (code "41") (name "/JOY1_UP") (class "Default")
      (node (ref "R46") (pin "1") (pinfunction "1_1") (pintype "passive"))
      (node (ref "X5") (pin "1") (pinfunction "F_1") (pintype "passive"))
    )
    (net (code "42") (name "/N$99") (class "Default")
      (node (ref "SV1") (pin "3") (pinfunction "3_3") (pintype "passive"))
      (node (ref "U1") (pin "P40") (pinfunction "IO_L01P_5CS_B_P40") (pintype "bidirectional"))
    )
    (net (code "43") (name "/N$100") (class "Default")
      (node (ref "SV1") (pin "4") (pinfunction "4_4") (pintype "passive"))
      (node (ref "U1") (pin "P41") (pinfunction "IO_L01N_5RDWR_B_P41") (pintype "bidirectional"))
    )
    (net (code "44") (name "/N$101") (class "Default")
      (node (ref "SV1") (pin "5") (pinfunction "5_5") (pintype "passive"))
      (node (ref "U1") (pin "P44") (pinfunction "IOVREF_5_P44") (pintype "bidirectional"))
    )
    (net (code "45") (name "/PC2") (class "Default")
      (node (ref "IC3") (pin "5") (pinfunction "PC2(AIN2/PCIN11)_5") (pintype "bidirectional"))
      (node (ref "U1") (pin "P100") (pinfunction "IO_L22N_2_P100") (pintype "bidirectional"))
    )
    (net (code "46") (name "/PC4") (class "Default")
      (node (ref "IC3") (pin "26") (pinfunction "PC4(PCINT10)_26") (pintype "bidirectional"))
      (node (ref "SV4") (pin "1") (pinfunction "1_1") (pintype "passive"))
    )
    (net (code "47") (name "/PC5") (class "Default")
      (node (ref "IC3") (pin "25") (pinfunction "PC5(OC1B/PCINT9)_25") (pintype "bidirectional"))
      (node (ref "SV4") (pin "2") (pinfunction "2_2") (pintype "passive"))
    )
    (net (code "48") (name "/PD0") (class "Default")
      (node (ref "IC3") (pin "6") (pinfunction "PD0(INT0/OC0B)_6") (pintype "bidirectional"))
      (node (ref "U1") (pin "P99") (pinfunction "IO_L22P_2_P99") (pintype "bidirectional"))
    )
    (net (code "49") (name "/PD1") (class "Default")
      (node (ref "IC3") (pin "7") (pinfunction "PD1(INT1/AIN0)_7") (pintype "bidirectional"))
      (node (ref "U1") (pin "P98") (pinfunction "IO_L23N_2VREF_2_P98") (pintype "bidirectional"))
    )
    (net (code "50") (name "/PD2") (class "Default")
      (node (ref "IC3") (pin "8") (pinfunction "PD2(INT2/AIN1/RXD1)_8") (pintype "bidirectional"))
      (node (ref "U1") (pin "P97") (pinfunction "IO_L23P_2_P97") (pintype "bidirectional"))
    )
    (net (code "51") (name "/PD3") (class "Default")
      (node (ref "IC3") (pin "9") (pinfunction "PD3(INT3/TXD1)_9") (pintype "bidirectional"))
      (node (ref "U1") (pin "P95") (pinfunction "IO_L24P_2_P95") (pintype "bidirectional"))
    )
    (net (code "52") (name "/PD4") (class "Default")
      (node (ref "IC3") (pin "10") (pinfunction "PD4(INT5/AIN3)_10") (pintype "bidirectional"))
      (node (ref "U1") (pin "P93") (pinfunction "IO_L40N_2_P93") (pintype "bidirectional"))
    )
    (net (code "53") (name "/PD5") (class "Default")
      (node (ref "IC3") (pin "11") (pinfunction "PD5(XCK/AIN4/PCINT12)_11") (pintype "bidirectional"))
      (node (ref "U1") (pin "P92") (pinfunction "IO_L40P_2VREF_2_P92") (pintype "bidirectional"))
    )
    (net (code "54") (name "/PD6") (class "Default")
      (node (ref "IC3") (pin "12") (pinfunction "PD6(INT6/AIN5/RTS)_12") (pintype "bidirectional"))
      (node (ref "U1") (pin "P96") (pinfunction "IO_L24N_2_P96") (pintype "bidirectional"))
    )
    (net (code "55") (name "/PROM_DO") (class "Default")
      (node (ref "IC1") (pin "1") (pinfunction "DO_1") (pintype "bidirectional"))
      (node (ref "U1") (pin "P65") (pinfunction "IO_L27N_4DIND0_P65") (pintype "bidirectional"))
    )
    (net (code "56") (name "/PROM_INITB") (class "Default")
      (node (ref "IC1") (pin "8") (pinfunction "OE/RESET_8") (pintype "bidirectional"))
      (node (ref "U1") (pin "P58") (pinfunction "IO_L31N_4INIT_B_P58") (pintype "bidirectional"))
    )
    (net (code "57") (name "/PS2CLK") (class "Default")
      (node (ref "R4") (pin "1") (pinfunction "1_1") (pintype "passive"))
      (node (ref "R47") (pin "2") (pinfunction "2_2") (pintype "passive"))
      (node (ref "T1") (pin "2") (pinfunction "S_2") (pintype "passive"))
      (node (ref "U1") (pin "P141") (pinfunction "IO_L01N_0VRP_0_P141") (pintype "bidirectional"))
    )
    (net (code "58") (name "/PS2DAT") (class "Default")
      (node (ref "R51") (pin "2") (pinfunction "2_2") (pintype "passive"))
      (node (ref "R6") (pin "1") (pinfunction "1_1") (pintype "passive"))
      (node (ref "T3") (pin "2") (pinfunction "S_2") (pintype "passive"))
      (node (ref "U1") (pin "P140") (pinfunction "IO_L01P_0VRN_0_P140") (pintype "bidirectional"))
    )
    (net (code "59") (name "/R0") (class "Default")
      (node (ref "R10") (pin "1") (pinfunction "1_1") (pintype "passive"))
      (node (ref "U1") (pin "P56") (pinfunction "IO_L32N_4GCLK1_P56") (pintype "bidirectional"))
    )
    (net (code "60") (name "/R1") (class "Default")
      (node (ref "R9") (pin "1") (pinfunction "1_1") (pintype "passive"))
      (node (ref "U1") (pin "P53") (pinfunction "IO_L32N_5GCLK3_P53") (pintype "bidirectional"))
    )
    (net (code "61") (name "/RESET") (class "Default")
      (node (ref "R52") (pin "2") (pinfunction "2_2") (pintype "passive"))
      (node (ref "RESET_SW") (pin "1") (pinfunction "1_1") (pintype "passive"))
    )
    (net (code "62") (name "/SAA") (class "Default")
      (node (ref "SV1") (pin "9") (pinfunction "9_9") (pintype "passive"))
      (node (ref "U1") (pin "P52") (pinfunction "IO_L32P_5GCLK2_P52") (pintype "bidirectional"))
    )
    (net (code "63") (name "/SCART_BLANKING") (class "Default")
      (node (ref "R50") (pin "1") (pinfunction "1_1") (pintype "passive"))
      (node (ref "X1") (pin "16") (pinfunction "16_16") (pintype "passive"))
    )
    (net (code "64") (name "/SCART_BLUE") (class "Default")
      (node (ref "R31") (pin "1") (pinfunction "1_1") (pintype "passive"))
      (node (ref "R32") (pin "1") (pinfunction "1_1") (pintype "passive"))
      (node (ref "R33") (pin "1") (pinfunction "1_1") (pintype "passive"))
      (node (ref "X1") (pin "7") (pinfunction "7_7") (pintype "passive"))
    )
    (net (code "65") (name "/SCART_COMP") (class "Default")
      (node (ref "R13") (pin "1") (pinfunction "1_1") (pintype "passive"))
      (node (ref "R14") (pin "1") (pinfunction "1_1") (pintype "passive"))
      (node (ref "X1") (pin "19") (pinfunction "19_19") (pintype "passive"))
    )
    (net (code "66") (name "/SCART_GREEN") (class "Default")
      (node (ref "R26") (pin "1") (pinfunction "1_1") (pintype "passive"))
      (node (ref "R27") (pin "1") (pinfunction "1_1") (pintype "passive"))
      (node (ref "R28") (pin "1") (pinfunction "1_1") (pintype "passive"))
      (node (ref "X1") (pin "11") (pinfunction "11_11") (pintype "passive"))
    )
    (net (code "67") (name "/SCART_LEFT") (class "Default")
      (node (ref "C3") (pin "2") (pinfunction "2_2") (pintype "passive"))
      (node (ref "X1") (pin "3") (pinfunction "3_3") (pintype "passive"))
    )
    (net (code "68") (name "/SCART_MODE") (class "Default")
      (node (ref "X1") (pin "8") (pinfunction "8_8") (pintype "passive"))
    )
    (net (code "69") (name "/SCART_RED") (class "Default")
      (node (ref "R15") (pin "1") (pinfunction "1_1") (pintype "passive"))
      (node (ref "R16") (pin "1") (pinfunction "1_1") (pintype "passive"))
      (node (ref "R20") (pin "1") (pinfunction "1_1") (pintype "passive"))
      (node (ref "X1") (pin "15") (pinfunction "15_15") (pintype "passive"))
    )
    (net (code "70") (name "/SCART_RIGHT") (class "Default")
      (node (ref "C4") (pin "2") (pinfunction "2_2") (pintype "passive"))
      (node (ref "X1") (pin "1") (pinfunction "1_1") (pintype "passive"))
    )
    (net (code "71") (name "/SPI_MISO") (class "Default")
      (node (ref "IC3") (pin "17") (pinfunction "PB3(PDO/MISO/PCINT3)_17") (pintype "bidirectional"))
      (node (ref "SV2") (pin "4") (pinfunction "4_4") (pintype "passive"))
    )
    (net (code "72") (name "/SPI_MOSI") (class "Default")
      (node (ref "IC3") (pin "16") (pinfunction "PB2(PDI/MOSI/PCINT2)_16") (pintype "bidirectional"))
      (node (ref "SV2") (pin "2") (pinfunction "2_2") (pintype "passive"))
    )
    (net (code "73") (name "/SPI_SCLK") (class "Default")
      (node (ref "IC3") (pin "15") (pinfunction "PB1(SCK/PCINT1)_15") (pintype "bidirectional"))
      (node (ref "SV2") (pin "3") (pinfunction "3_3") (pintype "passive"))
    )
    (net (code "74") (name "/SPI_SEL") (class "Default")
      (node (ref "IC3") (pin "14") (pinfunction "PB0(SS/PCINT0)_14") (pintype "bidirectional"))
      (node (ref "SV2") (pin "1") (pinfunction "1_1") (pintype "passive"))
    )
    (net (code "75") (name "/TCK") (class "Default")
      (node (ref "IC1") (pin "6") (pinfunction "TCK_6") (pintype "bidirectional"))
      (node (ref "IC3") (pin "19") (pinfunction "PB5(PCINT5)_19") (pintype "bidirectional"))
      (node (ref "R2") (pin "2") (pinfunction "2_2") (pintype "passive"))
      (node (ref "SV4") (pin "7") (pinfunction "7_7") (pintype "passive"))
    )
    (net (code "76") (name "/TDI_FPGA") (class "Default")
      (node (ref "IC3") (pin "21") (pinfunction "PB7(OC0A/OC1C/PCINT7)_21") (pintype "bidirectional"))
      (node (ref "R1") (pin "2") (pinfunction "2_2") (pintype "passive"))
      (node (ref "SV4") (pin "4") (pinfunction "4_4") (pintype "passive"))
    )
    (net (code "77") (name "/TDO_EXP") (class "Default")
      (node (ref "IC3") (pin "23") (pinfunction "PC6(OC1A/PCINT8)_23") (pintype "bidirectional"))
      (node (ref "SV4") (pin "3") (pinfunction "3_3") (pintype "passive"))
    )
    (net (code "78") (name "/TDO_PROM") (class "Default")
      (node (ref "IC1") (pin "17") (pinfunction "TDO_17") (pintype "bidirectional"))
      (node (ref "IC3") (pin "20") (pinfunction "PB6(PCINT6)_20") (pintype "bidirectional"))
      (node (ref "SV4") (pin "5") (pinfunction "5_5") (pintype "passive"))
    )
    (net (code "79") (name "/TMS") (class "Default")
      (node (ref "IC1") (pin "5") (pinfunction "TMS_5") (pintype "bidirectional"))
      (node (ref "IC3") (pin "18") (pinfunction "PB4(T1/PCINT4)_18") (pintype "bidirectional"))
      (node (ref "R3") (pin "2") (pinfunction "2_2") (pintype "passive"))
      (node (ref "SV4") (pin "9") (pinfunction "9_9") (pintype "passive"))
    )
    (net (code "80") (name "/VCC") (class "Default")
      (node (ref "C10") (pin "1") (pinfunction "1_1") (pintype "passive"))
      (node (ref "C11") (pin "1") (pinfunction "1_1") (pintype "passive"))
      (node (ref "C12") (pin "1") (pinfunction "1_1") (pintype "passive"))
      (node (ref "C13") (pin "1") (pinfunction "1_1") (pintype "passive"))
      (node (ref "C14") (pin "1") (pinfunction "1_1") (pintype "passive"))
      (node (ref "C15") (pin "1") (pinfunction "1_1") (pintype "passive"))
      (node (ref "C16") (pin "1") (pinfunction "1_1") (pintype "passive"))
      (node (ref "C17") (pin "1") (pinfunction "1_1") (pintype "passive"))
      (node (ref "C26") (pin "1") (pinfunction "1_1") (pintype "passive"))
      (node (ref "C27") (pin "1") (pinfunction "1_1") (pintype "passive"))
      (node (ref "C28") (pin "1") (pinfunction "1_1") (pintype "passive"))
      (node (ref "C29") (pin "1") (pinfunction "1_1") (pintype "passive"))
      (node (ref "C30") (pin "1") (pinfunction "1_1") (pintype "passive"))
      (node (ref "C31") (pin "1") (pinfunction "1_1") (pintype "passive"))
      (node (ref "C32") (pin "1") (pinfunction "1_1") (pintype "passive"))
      (node (ref "C34") (pin "1") (pinfunction "1_1") (pintype "passive"))
      (node (ref "C6") (pin "1") (pinfunction "1_1") (pintype "passive"))
      (node (ref "C7") (pin "1") (pinfunction "1_1") (pintype "passive"))
      (node (ref "C8") (pin "1") (pinfunction "1_1") (pintype "passive"))
      (node (ref "C9") (pin "1") (pinfunction "1_1") (pintype "passive"))
      (node (ref "IC1") (pin "18") (pinfunction "VCCINT_18") (pintype "bidirectional"))
      (node (ref "IC1") (pin "19") (pinfunction "VCCO_19") (pintype "bidirectional"))
      (node (ref "IC1") (pin "20") (pinfunction "VCCJ_20") (pintype "bidirectional"))
      (node (ref "IC2") (pin "8") (pinfunction "VCC_8") (pintype "power_in"))
      (node (ref "IC3") (pin "31") (pinfunction "UVCC_31") (pintype "bidirectional"))
      (node (ref "IC3") (pin "32") (pinfunction "AVCC_32") (pintype "bidirectional"))
      (node (ref "IC3") (pin "4") (pinfunction "VCC_4") (pintype "bidirectional"))
      (node (ref "JP1") (pin "2") (pinfunction "2_2") (pintype "passive"))
      (node (ref "Q5") (pin "3") (pinfunction "C_3") (pintype "passive"))
      (node (ref "Q6") (pin "3") (pinfunction "C_3") (pintype "passive"))
      (node (ref "Q7") (pin "3") (pinfunction "C_3") (pintype "passive"))
      (node (ref "Q8") (pin "3") (pinfunction "C_3") (pintype "passive"))
      (node (ref "R22") (pin "1") (pinfunction "1_1") (pintype "passive"))
      (node (ref "R35") (pin "2") (pinfunction "2_2") (pintype "passive"))
      (node (ref "R36") (pin "2") (pinfunction "2_2") (pintype "passive"))
      (node (ref "R37") (pin "2") (pinfunction "2_2") (pintype "passive"))
      (node (ref "R38") (pin "2") (pinfunction "2_2") (pintype "passive"))
      (node (ref "R39") (pin "2") (pinfunction "2_2") (pintype "passive"))
      (node (ref "R4") (pin "2") (pinfunction "2_2") (pintype "passive"))
      (node (ref "R40") (pin "1") (pinfunction "1_1") (pintype "passive"))
      (node (ref "R41") (pin "1") (pinfunction "1_1") (pintype "passive"))
      (node (ref "R42") (pin "1") (pinfunction "1_1") (pintype "passive"))
      (node (ref "R43") (pin "1") (pinfunction "1_1") (pintype "passive"))
      (node (ref "R44") (pin "1") (pinfunction "1_1") (pintype "passive"))
      (node (ref "R45") (pin "1") (pinfunction "1_1") (pintype "passive"))
      (node (ref "R46") (pin "2") (pinfunction "2_2") (pintype "passive"))
      (node (ref "R52") (pin "1") (pinfunction "1_1") (pintype "passive"))
      (node (ref "R55") (pin "1") (pinfunction "1_1") (pintype "passive"))
      (node (ref "R6") (pin "2") (pinfunction "2_2") (pintype "passive"))
      (node (ref "SV1") (pin "1") (pinfunction "1_1") (pintype "passive"))
      (node (ref "SV2") (pin "5") (pinfunction "5_5") (pintype "passive"))
      (node (ref "SV3") (pin "1") (pinfunction "1_1") (pintype "passive"))
      (node (ref "SV4") (pin "10") (pinfunction "10_10") (pintype "passive"))
      (node (ref "T1") (pin "3") (pinfunction "G_3") (pintype "passive"))
      (node (ref "T2") (pin "3") (pinfunction "C_3") (pintype "passive"))
      (node (ref "T3") (pin "3") (pinfunction "G_3") (pintype "passive"))
      (node (ref "U$2") (pin "VDD") (pinfunction "VDD_VDD") (pintype "power_in"))
      (node (ref "U$4") (pin "4") (pinfunction "VOUT1_4") (pintype "bidirectional"))
      (node (ref "U$5") (pin "2") (pinfunction "VOUT1_2") (pintype "output"))
      (node (ref "U$5") (pin "3") (pinfunction "VOUT2_3") (pintype "output"))
      (node (ref "U$5") (pin "6") (pinfunction "VOUT3_6") (pintype "output"))
      (node (ref "U$5") (pin "7") (pinfunction "VOUT4_7") (pintype "output"))
      (node (ref "U$6") (pin "P8") (pinfunction "VCC_P8") (pintype "bidirectional"))
      (node (ref "U1") (pin "P106") (pinfunction "VCCO_RIGHT2_P106") (pintype "passive"))
      (node (ref "U1") (pin "P115") (pinfunction "VCCO_TOP0_P115") (pintype "passive"))
      (node (ref "U1") (pin "P126") (pinfunction "VCCO_TOP1_P126") (pintype "passive"))
      (node (ref "U1") (pin "P138") (pinfunction "VCCO_TOP2_P138") (pintype "passive"))
      (node (ref "U1") (pin "P19") (pinfunction "VCCO_LEFT1_P19") (pintype "passive"))
      (node (ref "U1") (pin "P3") (pinfunction "VCCO_LEFT0_P3") (pintype "passive"))
      (node (ref "U1") (pin "P34") (pinfunction "VCCO_LEFT2_P34") (pintype "passive"))
      (node (ref "U1") (pin "P43") (pinfunction "VCCO_BOTTOM0_P43") (pintype "passive"))
      (node (ref "U1") (pin "P54") (pinfunction "VCCO_BOTTOM1_P54") (pintype "passive"))
      (node (ref "U1") (pin "P66") (pinfunction "VCCO_BOTTOM2_P66") (pintype "passive"))
      (node (ref "U1") (pin "P75") (pinfunction "VCCO_RIGHT0_P75") (pintype "passive"))
      (node (ref "U1") (pin "P91") (pinfunction "VCCO_RIGHT1_P91") (pintype "passive"))
    )
    (net (code "81") (name "/VCC5") (class "Default")
      (node (ref "C33") (pin "+") (pinfunction "+_+") (pintype "passive"))
      (node (ref "C35") (pin "+") (pinfunction "+_+") (pintype "passive"))
      (node (ref "C36") (pin "+") (pinfunction "+_+") (pintype "passive"))
      (node (ref "PWR_HDR") (pin "2") (pinfunction "2_2") (pintype "passive"))
      (node (ref "R5") (pin "2") (pinfunction "2_2") (pintype "passive"))
      (node (ref "R7") (pin "2") (pinfunction "2_2") (pintype "passive"))
      (node (ref "REG1.2") (pin "3") (pinfunction "VCC_3") (pintype "bidirectional"))
      (node (ref "REG2.5") (pin "3") (pinfunction "VCC_3") (pintype "bidirectional"))
      (node (ref "U$4") (pin "3") (pinfunction "VCC_3") (pintype "bidirectional"))
      (node (ref "U$5") (pin "4") (pinfunction "VCC_4") (pintype "bidirectional"))
      (node (ref "X3") (pin "5") (pinfunction "5_5") (pintype "passive"))
      (node (ref "X7") (pin "2") (pinfunction "2_2") (pintype "power_in"))
    )
    (net (code "82") (name "/VCCAUX") (class "Default")
      (node (ref "C18") (pin "1") (pinfunction "1_1") (pintype "passive"))
      (node (ref "C19") (pin "1") (pinfunction "1_1") (pintype "passive"))
      (node (ref "C20") (pin "1") (pinfunction "1_1") (pintype "passive"))
      (node (ref "C21") (pin "1") (pinfunction "1_1") (pintype "passive"))
      (node (ref "R50") (pin "2") (pinfunction "2_2") (pintype "passive"))
      (node (ref "REG2.5") (pin "4") (pinfunction "VOUT1_4") (pintype "bidirectional"))
      (node (ref "U1") (pin "P120") (pinfunction "VCCAUX2_P120") (pintype "passive"))
      (node (ref "U1") (pin "P134") (pinfunction "VCCAUX3_P134") (pintype "passive"))
      (node (ref "U1") (pin "P48") (pinfunction "VCCAUX0_P48") (pintype "passive"))
      (node (ref "U1") (pin "P62") (pinfunction "VCCAUX1_P62") (pintype "passive"))
    )
    (net (code "83") (name "/VCCINT") (class "Default")
      (node (ref "C22") (pin "1") (pinfunction "1_1") (pintype "passive"))
      (node (ref "C23") (pin "1") (pinfunction "1_1") (pintype "passive"))
      (node (ref "C24") (pin "1") (pinfunction "1_1") (pintype "passive"))
      (node (ref "C25") (pin "1") (pinfunction "1_1") (pintype "passive"))
      (node (ref "REG1.2") (pin "4") (pinfunction "VOUT1_4") (pintype "bidirectional"))
      (node (ref "U1") (pin "P121") (pinfunction "VCCINT2_P121") (pintype "passive"))
      (node (ref "U1") (pin "P133") (pinfunction "VCCINT3_P133") (pintype "passive"))
      (node (ref "U1") (pin "P49") (pinfunction "VCCINT0_P49") (pintype "passive"))
      (node (ref "U1") (pin "P61") (pinfunction "VCCINT1_P61") (pintype "passive"))
    )
    (net (code "84") (name "/VCC_B3") (class "Default")
      (node (ref "R11") (pin "2") (pinfunction "2_2") (pintype "passive"))
    )
    (net (code "86") (name "GND") (class "Default")
      (node (ref "C1") (pin "1") (pinfunction "1_1") (pintype "passive"))
      (node (ref "C10") (pin "2") (pinfunction "2_2") (pintype "passive"))
      (node (ref "C11") (pin "2") (pinfunction "2_2") (pintype "passive"))
      (node (ref "C12") (pin "2") (pinfunction "2_2") (pintype "passive"))
      (node (ref "C13") (pin "2") (pinfunction "2_2") (pintype "passive"))
      (node (ref "C14") (pin "2") (pinfunction "2_2") (pintype "passive"))
      (node (ref "C15") (pin "2") (pinfunction "2_2") (pintype "passive"))
      (node (ref "C16") (pin "2") (pinfunction "2_2") (pintype "passive"))
      (node (ref "C17") (pin "2") (pinfunction "2_2") (pintype "passive"))
      (node (ref "C18") (pin "2") (pinfunction "2_2") (pintype "passive"))
      (node (ref "C19") (pin "2") (pinfunction "2_2") (pintype "passive"))
      (node (ref "C20") (pin "2") (pinfunction "2_2") (pintype "passive"))
      (node (ref "C21") (pin "2") (pinfunction "2_2") (pintype "passive"))
      (node (ref "C22") (pin "2") (pinfunction "2_2") (pintype "passive"))
      (node (ref "C23") (pin "2") (pinfunction "2_2") (pintype "passive"))
      (node (ref "C24") (pin "2") (pinfunction "2_2") (pintype "passive"))
      (node (ref "C25") (pin "2") (pinfunction "2_2") (pintype "passive"))
      (node (ref "C26") (pin "2") (pinfunction "2_2") (pintype "passive"))
      (node (ref "C27") (pin "2") (pinfunction "2_2") (pintype "passive"))
      (node (ref "C28") (pin "2") (pinfunction "2_2") (pintype "passive"))
      (node (ref "C29") (pin "2") (pinfunction "2_2") (pintype "passive"))
      (node (ref "C30") (pin "2") (pinfunction "2_2") (pintype "passive"))
      (node (ref "C31") (pin "2") (pinfunction "2_2") (pintype "passive"))
      (node (ref "C32") (pin "2") (pinfunction "2_2") (pintype "passive"))
      (node (ref "C33") (pin "-") (pinfunction "-_-") (pintype "passive"))
      (node (ref "C34") (pin "2") (pinfunction "2_2") (pintype "passive"))
      (node (ref "C35") (pin "-") (pinfunction "-_-") (pintype "passive"))
      (node (ref "C36") (pin "-") (pinfunction "-_-") (pintype "passive"))
      (node (ref "C37") (pin "1") (pinfunction "1_1") (pintype "passive"))
      (node (ref "C38") (pin "1") (pinfunction "1_1") (pintype "passive"))
      (node (ref "C39") (pin "-") (pinfunction "-_-") (pintype "passive"))
      (node (ref "C40") (pin "-") (pinfunction "-_-") (pintype "passive"))
      (node (ref "C41") (pin "2") (pinfunction "2_2") (pintype "passive"))
      (node (ref "C5") (pin "1") (pinfunction "1_1") (pintype "passive"))
      (node (ref "C6") (pin "2") (pinfunction "2_2") (pintype "passive"))
      (node (ref "C7") (pin "2") (pinfunction "2_2") (pintype "passive"))
      (node (ref "C8") (pin "2") (pinfunction "2_2") (pintype "passive"))
      (node (ref "C9") (pin "2") (pinfunction "2_2") (pintype "passive"))
      (node (ref "IC1") (pin "11") (pinfunction "GND_11") (pintype "bidirectional"))
      (node (ref "IC2") (pin "4") (pinfunction "GND_4") (pintype "power_in"))
      (node (ref "IC3") (pin "3") (pinfunction "GND_3") (pintype "bidirectional"))
      (node (ref "JP1") (pin "1") (pinfunction "1_1") (pintype "passive"))
      (node (ref "PWR_HDR") (pin "1") (pinfunction "1_1") (pintype "passive"))
      (node (ref "R12") (pin "1") (pinfunction "1_1") (pintype "passive"))
      (node (ref "R17") (pin "1") (pinfunction "1_1") (pintype "passive"))
      (node (ref "R19") (pin "1") (pinfunction "1_1") (pintype "passive"))
      (node (ref "R21") (pin "1") (pinfunction "1_1") (pintype "passive"))
      (node (ref "REG1.2") (pin "1") (pinfunction "GND_1") (pintype "bidirectional"))
      (node (ref "REG2.5") (pin "1") (pinfunction "GND_1") (pintype "bidirectional"))
      (node (ref "RESET_SW") (pin "2") (pinfunction "2_2") (pintype "passive"))
      (node (ref "SV1") (pin "2") (pinfunction "2_2") (pintype "passive"))
      (node (ref "SV2") (pin "6") (pinfunction "6_6") (pintype "passive"))
      (node (ref "SV3") (pin "2") (pinfunction "2_2") (pintype "passive"))
      (node (ref "SV4") (pin "11") (pinfunction "11_11") (pintype "passive"))
      (node (ref "SV4") (pin "8") (pinfunction "8_8") (pintype "passive"))
      (node (ref "U$2") (pin "GND") (pinfunction "GND_GND") (pintype "power_in"))
      (node (ref "U$4") (pin "1") (pinfunction "GND_1") (pintype "bidirectional"))
      (node (ref "U$5") (pin "1") (pinfunction "GND_1") (pintype "bidirectional"))
      (node (ref "U$6") (pin "P24") (pinfunction "VSS_P24") (pintype "bidirectional"))
      (node (ref "U$6") (pin "P30") (pinfunction "CE_P30") (pintype "bidirectional"))
      (node (ref "U1") (pin "P101") (pinfunction "GND11_P101") (pintype "passive"))
      (node (ref "U1") (pin "P114") (pinfunction "GND12_P114") (pintype "passive"))
      (node (ref "U1") (pin "P117") (pinfunction "GND13_P117") (pintype "passive"))
      (node (ref "U1") (pin "P136") (pinfunction "GND14_P136") (pintype "passive"))
      (node (ref "U1") (pin "P139") (pinfunction "GND15_P139") (pintype "passive"))
      (node (ref "U1") (pin "P16") (pinfunction "GND1_P16") (pintype "passive"))
      (node (ref "U1") (pin "P22") (pinfunction "GND2_P22") (pintype "passive"))
      (node (ref "U1") (pin "P29") (pinfunction "GND3_P29") (pintype "passive"))
      (node (ref "U1") (pin "P37") (pinfunction "M1_P37") (pintype "bidirectional"))
      (node (ref "U1") (pin "P38") (pinfunction "M0_P38") (pintype "bidirectional"))
      (node (ref "U1") (pin "P39") (pinfunction "M2_P39") (pintype "bidirectional"))
      (node (ref "U1") (pin "P42") (pinfunction "GND4_P42") (pintype "passive"))
      (node (ref "U1") (pin "P45") (pinfunction "GND5_P45") (pintype "passive"))
      (node (ref "U1") (pin "P64") (pinfunction "GND6_P64") (pintype "passive"))
      (node (ref "U1") (pin "P67") (pinfunction "GND7_P67") (pintype "passive"))
      (node (ref "U1") (pin "P81") (pinfunction "GND8_P81") (pintype "passive"))
      (node (ref "U1") (pin "P88") (pinfunction "GND9_P88") (pintype "passive"))
      (node (ref "U1") (pin "P9") (pinfunction "GND0_P9") (pintype "passive"))
      (node (ref "U1") (pin "P94") (pinfunction "GND10_P94") (pintype "passive"))
      (node (ref "X1") (pin "13") (pinfunction "13_13") (pintype "passive"))
      (node (ref "X1") (pin "14") (pinfunction "14_14") (pintype "passive"))
      (node (ref "X1") (pin "17") (pinfunction "17_17") (pintype "passive"))
      (node (ref "X1") (pin "18") (pinfunction "18_18") (pintype "passive"))
      (node (ref "X1") (pin "21") (pinfunction "21_21") (pintype "passive"))
      (node (ref "X1") (pin "4") (pinfunction "4_4") (pintype "passive"))
      (node (ref "X1") (pin "5") (pinfunction "5_5") (pintype "passive"))
      (node (ref "X1") (pin "9") (pinfunction "9_9") (pintype "passive"))
      (node (ref "X3") (pin "3") (pinfunction "3_3") (pintype "passive"))
      (node (ref "X3") (pin "SH1") (pinfunction "PE1_SH1") (pintype "power_in"))
      (node (ref "X3") (pin "SH2") (pinfunction "PE2_SH2") (pintype "power_in"))
      (node (ref "X3") (pin "SH3") (pinfunction "PE3_SH3") (pintype "power_in"))
      (node (ref "X4") (pin "8") (pinfunction "F_8") (pintype "passive"))
      (node (ref "X4") (pin "G1") (pinfunction "G1_G1") (pintype "passive"))
      (node (ref "X5") (pin "8") (pinfunction "F_8") (pintype "passive"))
      (node (ref "X5") (pin "G1") (pinfunction "G1_G1") (pintype "passive"))
      (node (ref "X7") (pin "3") (pinfunction "3_3") (pintype "power_in"))
      (node (ref "X8") (pin "1") (pinfunction "1_1") (pintype "passive"))
    )
    (net (code "87") (name "Net-(C1-Pad2)") (class "Default")
      (node (ref "C1") (pin "2") (pinfunction "2_2") (pintype "passive"))
      (node (ref "R23") (pin "2") (pinfunction "2_2") (pintype "passive"))
      (node (ref "R48") (pin "1") (pinfunction "1_1") (pintype "passive"))
    )
    (net (code "88") (name "Net-(C2-Pad1)") (class "Default")
      (node (ref "C2") (pin "1") (pinfunction "1_1") (pintype "passive"))
      (node (ref "R17") (pin "2") (pinfunction "2_2") (pintype "passive"))
      (node (ref "X8") (pin "2") (pinfunction "2_2") (pintype "passive"))
      (node (ref "X8") (pin "3") (pinfunction "3_3") (pintype "passive"))
      (node (ref "X8") (pin "4") (pinfunction "4_4") (pintype "passive"))
      (node (ref "X8") (pin "5") (pinfunction "5_5") (pintype "passive"))
    )
    (net (code "89") (name "Net-(C3-Pad1)") (class "Default")
      (node (ref "C3") (pin "1") (pinfunction "1_1") (pintype "passive"))
      (node (ref "R48") (pin "2") (pinfunction "2_2") (pintype "passive"))
    )
    (net (code "90") (name "Net-(C4-Pad1)") (class "Default")
      (node (ref "C4") (pin "1") (pinfunction "1_1") (pintype "passive"))
      (node (ref "R49") (pin "2") (pinfunction "2_2") (pintype "passive"))
    )
    (net (code "91") (name "Net-(C5-Pad2)") (class "Default")
      (node (ref "C5") (pin "2") (pinfunction "2_2") (pintype "passive"))
      (node (ref "R34") (pin "2") (pinfunction "2_2") (pintype "passive"))
      (node (ref "R49") (pin "1") (pinfunction "1_1") (pintype "passive"))
    )
    (net (code "92") (name "Net-(IC1-CLK)") (class "Default")
      (node (ref "IC1") (pin "3") (pinfunction "CLK_3") (pintype "bidirectional"))
      (node (ref "U1") (pin "P72") (pinfunction "CCLK_P72") (pintype "bidirectional"))
    )
    (net (code "93") (name "Net-(IC1-TDI)") (class "Default")
      (node (ref "IC1") (pin "4") (pinfunction "TDI_4") (pintype "bidirectional"))
      (node (ref "U1") (pin "P109") (pinfunction "TDO_P109") (pintype "bidirectional"))
    )
    (net (code "94") (name "Net-(IC1-{slash}CE)") (class "Default")
      (node (ref "IC1") (pin "10") (pinfunction "/CE_10") (pintype "bidirectional"))
      (node (ref "U1") (pin "P71") (pinfunction "DONE_P71") (pintype "bidirectional"))
    )
    (net (code "95") (name "Net-(IC1-{slash}CF)") (class "Default")
      (node (ref "IC1") (pin "7") (pinfunction "/CF_7") (pintype "bidirectional"))
      (node (ref "U1") (pin "P143") (pinfunction "PROG_B_P143") (pintype "bidirectional"))
    )
    (net (code "96") (name "Net-(IC3-D+)") (class "Default")
      (node (ref "IC3") (pin "29") (pinfunction "D+_29") (pintype "bidirectional"))
      (node (ref "R54") (pin "2") (pinfunction "2_2") (pintype "passive"))
    )
    (net (code "97") (name "Net-(IC3-D-)") (class "Default")
      (node (ref "IC3") (pin "30") (pinfunction "D-_30") (pintype "bidirectional"))
      (node (ref "R53") (pin "2") (pinfunction "2_2") (pintype "passive"))
    )
    (net (code "98") (name "Net-(IC3-UCAP)") (class "Default")
      (node (ref "C41") (pin "1") (pinfunction "1_1") (pintype "passive"))
      (node (ref "IC3") (pin "27") (pinfunction "UCAP_27") (pintype "bidirectional"))
    )
    (net (code "99") (name "Net-(IC3-UGND)") (class "Default")
      (node (ref "IC3") (pin "28") (pinfunction "UGND_28") (pintype "bidirectional"))
      (node (ref "X6") (pin "4") (pinfunction "4_4") (pintype "passive"))
    )
    (net (code "100") (name "Net-(IC3-XTAL1)") (class "Default")
      (node (ref "C38") (pin "2") (pinfunction "2_2") (pintype "passive"))
      (node (ref "C39") (pin "+") (pinfunction "+_+") (pintype "passive"))
      (node (ref "IC3") (pin "1") (pinfunction "XTAL1_1") (pintype "bidirectional"))
      (node (ref "Q1") (pin "2") (pinfunction "2_2") (pintype "passive"))
    )
    (net (code "101") (name "Net-(IC3-XTAL2{slash}PC0)") (class "Default")
      (node (ref "C37") (pin "2") (pinfunction "2_2") (pintype "passive"))
      (node (ref "C40") (pin "+") (pinfunction "+_+") (pintype "passive"))
      (node (ref "IC3") (pin "2") (pinfunction "XTAL2/PC0_2") (pintype "bidirectional"))
      (node (ref "Q1") (pin "1") (pinfunction "1_1") (pintype "passive"))
    )
    (net (code "102") (name "Net-(Q5-B)") (class "Default")
      (node (ref "Q5") (pin "1") (pinfunction "B_1") (pintype "passive"))
      (node (ref "R8") (pin "2") (pinfunction "2_2") (pintype "passive"))
    )
    (net (code "103") (name "Net-(Q5-E)") (class "Default")
      (node (ref "Q5") (pin "2") (pinfunction "E_2") (pintype "passive"))
      (node (ref "R13") (pin "2") (pinfunction "2_2") (pintype "passive"))
      (node (ref "R14") (pin "2") (pinfunction "2_2") (pintype "passive"))
    )
    (net (code "104") (name "Net-(Q6-B)") (class "Default")
      (node (ref "Q6") (pin "1") (pinfunction "B_1") (pintype "passive"))
      (node (ref "R10") (pin "2") (pinfunction "2_2") (pintype "passive"))
      (node (ref "R9") (pin "2") (pinfunction "2_2") (pintype "passive"))
    )
    (net (code "105") (name "Net-(Q6-E)") (class "Default")
      (node (ref "Q6") (pin "2") (pinfunction "E_2") (pintype "passive"))
      (node (ref "R15") (pin "2") (pinfunction "2_2") (pintype "passive"))
      (node (ref "R16") (pin "2") (pinfunction "2_2") (pintype "passive"))
      (node (ref "R20") (pin "2") (pinfunction "2_2") (pintype "passive"))
    )
    (net (code "106") (name "Net-(Q7-B)") (class "Default")
      (node (ref "Q7") (pin "1") (pinfunction "B_1") (pintype "passive"))
      (node (ref "R29") (pin "2") (pinfunction "2_2") (pintype "passive"))
      (node (ref "R30") (pin "2") (pinfunction "2_2") (pintype "passive"))
    )
    (net (code "107") (name "Net-(Q7-E)") (class "Default")
      (node (ref "Q7") (pin "2") (pinfunction "E_2") (pintype "passive"))
      (node (ref "R31") (pin "2") (pinfunction "2_2") (pintype "passive"))
      (node (ref "R32") (pin "2") (pinfunction "2_2") (pintype "passive"))
      (node (ref "R33") (pin "2") (pinfunction "2_2") (pintype "passive"))
    )
    (net (code "108") (name "Net-(Q8-B)") (class "Default")
      (node (ref "Q8") (pin "1") (pinfunction "B_1") (pintype "passive"))
      (node (ref "R24") (pin "2") (pinfunction "2_2") (pintype "passive"))
      (node (ref "R25") (pin "2") (pinfunction "2_2") (pintype "passive"))
    )
    (net (code "109") (name "Net-(Q8-E)") (class "Default")
      (node (ref "Q8") (pin "2") (pinfunction "E_2") (pintype "passive"))
      (node (ref "R26") (pin "2") (pinfunction "2_2") (pintype "passive"))
      (node (ref "R27") (pin "2") (pinfunction "2_2") (pintype "passive"))
      (node (ref "R28") (pin "2") (pinfunction "2_2") (pintype "passive"))
    )
    (net (code "110") (name "Net-(R18-Pad2)") (class "Default")
      (node (ref "R18") (pin "2") (pinfunction "2_2") (pintype "passive"))
      (node (ref "R22") (pin "2") (pinfunction "2_2") (pintype "passive"))
    )
    (net (code "111") (name "Net-(R53-Pad1)") (class "Default")
      (node (ref "R53") (pin "1") (pinfunction "1_1") (pintype "passive"))
      (node (ref "X6") (pin "2") (pinfunction "2_2") (pintype "passive"))
    )
    (net (code "112") (name "Net-(R54-Pad1)") (class "Default")
      (node (ref "R54") (pin "1") (pinfunction "1_1") (pintype "passive"))
      (node (ref "X6") (pin "3") (pinfunction "3_3") (pintype "passive"))
    )
    (net (code "113") (name "Net-(T2-B)") (class "Default")
      (node (ref "C2") (pin "2") (pinfunction "2_2") (pintype "passive"))
      (node (ref "R18") (pin "1") (pinfunction "1_1") (pintype "passive"))
      (node (ref "R19") (pin "2") (pinfunction "2_2") (pintype "passive"))
      (node (ref "T2") (pin "1") (pinfunction "B_1") (pintype "passive"))
    )
    (net (code "114") (name "Net-(U$6-A0)") (class "Default")
      (node (ref "U$6") (pin "P20") (pinfunction "A0_P20") (pintype "bidirectional"))
      (node (ref "U1") (pin "P24") (pinfunction "IO_L24N_6VREF_6_P24") (pintype "bidirectional"))
    )
    (net (code "115") (name "Net-(U$6-A1)") (class "Default")
      (node (ref "U$6") (pin "P19") (pinfunction "A1_P19") (pintype "bidirectional"))
      (node (ref "U1") (pin "P23") (pinfunction "IO_L24P_6_P23") (pintype "bidirectional"))
    )
    (net (code "116") (name "Net-(U$6-A2)") (class "Default")
      (node (ref "U$6") (pin "P18") (pinfunction "A2_P18") (pintype "bidirectional"))
      (node (ref "U1") (pin "P21") (pinfunction "IO_L40N_6_P21") (pintype "bidirectional"))
    )
    (net (code "117") (name "Net-(U$6-A3)") (class "Default")
      (node (ref "U$6") (pin "P17") (pinfunction "A3_P17") (pintype "bidirectional"))
      (node (ref "U1") (pin "P20") (pinfunction "IO_L40P_6VREF_6_P20") (pintype "bidirectional"))
    )
    (net (code "118") (name "Net-(U$6-A4)") (class "Default")
      (node (ref "U$6") (pin "P16") (pinfunction "A4_P16") (pintype "bidirectional"))
      (node (ref "U1") (pin "P18") (pinfunction "IO_L40N_7VREF_7_P18") (pintype "bidirectional"))
    )
    (net (code "119") (name "Net-(U$6-A5)") (class "Default")
      (node (ref "U$6") (pin "P15") (pinfunction "A5_P15") (pintype "bidirectional"))
      (node (ref "U1") (pin "P17") (pinfunction "IO_L40P_7_P17") (pintype "bidirectional"))
    )
    (net (code "120") (name "Net-(U$6-A6)") (class "Default")
      (node (ref "U$6") (pin "P14") (pinfunction "A6_P14") (pintype "bidirectional"))
      (node (ref "U1") (pin "P15") (pinfunction "IO_L24N_7_P15") (pintype "bidirectional"))
    )
    (net (code "121") (name "Net-(U$6-A7)") (class "Default")
      (node (ref "U$6") (pin "P13") (pinfunction "A7_P13") (pintype "bidirectional"))
      (node (ref "U1") (pin "P14") (pinfunction "IO_L24P_7_P14") (pintype "bidirectional"))
    )
    (net (code "122") (name "Net-(U$6-A8)") (class "Default")
      (node (ref "U$6") (pin "P3") (pinfunction "A8_P3") (pintype "bidirectional"))
      (node (ref "U1") (pin "P4") (pinfunction "IOVREF_7_P4") (pintype "bidirectional"))
    )
    (net (code "123") (name "Net-(U$6-A9)") (class "Default")
      (node (ref "U$6") (pin "P2") (pinfunction "A9_P2") (pintype "bidirectional"))
      (node (ref "U1") (pin "P2") (pinfunction "IO_L01N_7VRP_7_P2") (pintype "bidirectional"))
    )
    (net (code "124") (name "Net-(U$6-A10)") (class "Default")
      (node (ref "U$6") (pin "P31") (pinfunction "A10_P31") (pintype "bidirectional"))
      (node (ref "U1") (pin "P35") (pinfunction "IO_L01P_6VRN_6_P35") (pintype "bidirectional"))
    )
    (net (code "125") (name "Net-(U$6-A11)") (class "Default")
      (node (ref "U$6") (pin "P1") (pinfunction "A11_P1") (pintype "bidirectional"))
      (node (ref "U1") (pin "P1") (pinfunction "IO_L01P_7VRN_7_P1") (pintype "bidirectional"))
    )
    (net (code "126") (name "Net-(U$6-A12)") (class "Default")
      (node (ref "U$6") (pin "P12") (pinfunction "A12_P12") (pintype "bidirectional"))
      (node (ref "U1") (pin "P13") (pinfunction "IO_L23N_7_P13") (pintype "bidirectional"))
    )
    (net (code "127") (name "Net-(U$6-A13)") (class "Default")
      (node (ref "U$6") (pin "P4") (pinfunction "A13_P4") (pintype "bidirectional"))
      (node (ref "U1") (pin "P5") (pinfunction "IO_L20P_7_P5") (pintype "bidirectional"))
    )
    (net (code "128") (name "Net-(U$6-A14)") (class "Default")
      (node (ref "U$6") (pin "P11") (pinfunction "A14_P11") (pintype "bidirectional"))
      (node (ref "U1") (pin "P12") (pinfunction "IO_L23P_7_P12") (pintype "bidirectional"))
    )
    (net (code "129") (name "Net-(U$6-A15)") (class "Default")
      (node (ref "U$6") (pin "P7") (pinfunction "A15_P7") (pintype "bidirectional"))
      (node (ref "U1") (pin "P8") (pinfunction "IO_L21N_7_P8") (pintype "bidirectional"))
    )
    (net (code "130") (name "Net-(U$6-A16)") (class "Default")
      (node (ref "U$6") (pin "P10") (pinfunction "A16_P10") (pintype "bidirectional"))
      (node (ref "U1") (pin "P11") (pinfunction "IO_L22N_7_P11") (pintype "bidirectional"))
    )
    (net (code "131") (name "Net-(U$6-A17)") (class "Default")
      (node (ref "U$6") (pin "P6") (pinfunction "A17_P6") (pintype "bidirectional"))
      (node (ref "U1") (pin "P7") (pinfunction "IO_L21P_7_P7") (pintype "bidirectional"))
    )
    (net (code "132") (name "Net-(U$6-A18)") (class "Default")
      (node (ref "U$6") (pin "P9") (pinfunction "A18_P9") (pintype "bidirectional"))
      (node (ref "U1") (pin "P10") (pinfunction "IO_L22P_7_P10") (pintype "bidirectional"))
    )
    (net (code "133") (name "Net-(U$6-DQ0)") (class "Default")
      (node (ref "U$6") (pin "P21") (pinfunction "DQ0_P21") (pintype "bidirectional"))
      (node (ref "U1") (pin "P25") (pinfunction "IO_L23P_6_P25") (pintype "bidirectional"))
    )
    (net (code "134") (name "Net-(U$6-DQ1)") (class "Default")
      (node (ref "U$6") (pin "P22") (pinfunction "DQ1_P22") (pintype "bidirectional"))
      (node (ref "U1") (pin "P26") (pinfunction "IO_L23N_6_P26") (pintype "bidirectional"))
    )
    (net (code "135") (name "Net-(U$6-DQ2)") (class "Default")
      (node (ref "U$6") (pin "P23") (pinfunction "DQ2_P23") (pintype "bidirectional"))
      (node (ref "U1") (pin "P27") (pinfunction "IO_L22P_6_P27") (pintype "bidirectional"))
    )
    (net (code "136") (name "Net-(U$6-DQ3)") (class "Default")
      (node (ref "U$6") (pin "P25") (pinfunction "DQ3_P25") (pintype "bidirectional"))
      (node (ref "U1") (pin "P28") (pinfunction "IO_L22N_6_P28") (pintype "bidirectional"))
    )
    (net (code "137") (name "Net-(U$6-DQ4)") (class "Default")
      (node (ref "U$6") (pin "P26") (pinfunction "DQ4_P26") (pintype "bidirectional"))
      (node (ref "U1") (pin "P30") (pinfunction "IO_L21P_6_P30") (pintype "bidirectional"))
    )
    (net (code "138") (name "Net-(U$6-DQ5)") (class "Default")
      (node (ref "U$6") (pin "P27") (pinfunction "DQ5_P27") (pintype "bidirectional"))
      (node (ref "U1") (pin "P31") (pinfunction "IO_L21N_6_P31") (pintype "bidirectional"))
    )
    (net (code "139") (name "Net-(U$6-DQ6)") (class "Default")
      (node (ref "U$6") (pin "P28") (pinfunction "DQ6_P28") (pintype "bidirectional"))
      (node (ref "U1") (pin "P32") (pinfunction "IO_L20P_6_P32") (pintype "bidirectional"))
    )
    (net (code "140") (name "Net-(U$6-DQ7)") (class "Default")
      (node (ref "U$6") (pin "P29") (pinfunction "DQ7_P29") (pintype "bidirectional"))
      (node (ref "U1") (pin "P33") (pinfunction "IO_L20N_6_P33") (pintype "bidirectional"))
    )
    (net (code "141") (name "Net-(U$6-OE)") (class "Default")
      (node (ref "U$6") (pin "P32") (pinfunction "OE_P32") (pintype "bidirectional"))
      (node (ref "U1") (pin "P36") (pinfunction "IO_L01N_6VRP_6_P36") (pintype "bidirectional"))
    )
    (net (code "142") (name "Net-(U$6-WE)") (class "Default")
      (node (ref "U$6") (pin "P5") (pinfunction "WE_P5") (pintype "bidirectional"))
      (node (ref "U1") (pin "P6") (pinfunction "IO_L20N_7_P6") (pintype "bidirectional"))
    )
    (net (code "143") (name "Net-(U1A-IO_L27N_0)") (class "Default")
      (node (ref "SV3") (pin "3") (pinfunction "3_3") (pintype "passive"))
      (node (ref "U1") (pin "P137") (pinfunction "IO_L27N_0_P137") (pintype "bidirectional"))
    )
    (net (code "144") (name "Net-(U1A-IO_L27P_0)") (class "Default")
      (node (ref "SV3") (pin "4") (pinfunction "4_4") (pintype "passive"))
      (node (ref "U1") (pin "P135") (pinfunction "IO_L27P_0_P135") (pintype "bidirectional"))
    )
    (net (code "145") (name "Net-(U1A-IO_L30N_0)") (class "Default")
      (node (ref "SV3") (pin "5") (pinfunction "5_5") (pintype "passive"))
      (node (ref "U1") (pin "P132") (pinfunction "IO_L30N_0_P132") (pintype "bidirectional"))
    )
    (net (code "146") (name "Net-(U1A-IO_L30P_0)") (class "Default")
      (node (ref "SV3") (pin "6") (pinfunction "6_6") (pintype "passive"))
      (node (ref "U1") (pin "P131") (pinfunction "IO_L30P_0_P131") (pintype "bidirectional"))
    )
    (net (code "147") (name "Net-(U1A-IO_L31N_0)") (class "Default")
      (node (ref "SV3") (pin "7") (pinfunction "7_7") (pintype "passive"))
      (node (ref "U1") (pin "P130") (pinfunction "IO_L31N_0_P130") (pintype "bidirectional"))
    )
    (net (code "148") (name "Net-(U1A-IO_L31P_0VREF_0)") (class "Default")
      (node (ref "SV3") (pin "8") (pinfunction "8_8") (pintype "passive"))
      (node (ref "U1") (pin "P129") (pinfunction "IO_L31P_0VREF_0_P129") (pintype "bidirectional"))
    )
    (net (code "149") (name "Net-(U1A-IO_L32N_0GCLK7)") (class "Default")
      (node (ref "SV3") (pin "9") (pinfunction "9_9") (pintype "passive"))
      (node (ref "U1") (pin "P128") (pinfunction "IO_L32N_0GCLK7_P128") (pintype "bidirectional"))
    )
    (net (code "150") (name "Net-(U1C-IO_L32N_1GCLK5)") (class "Default")
      (node (ref "SV3") (pin "10") (pinfunction "10_10") (pintype "passive"))
      (node (ref "U1") (pin "P125") (pinfunction "IO_L32N_1GCLK5_P125") (pintype "bidirectional"))
    )
    (net (code "151") (name "Net-(U1G-IO_L32P_4GCLK0)") (class "Default")
      (node (ref "SV1") (pin "10") (pinfunction "10_10") (pintype "passive"))
      (node (ref "U1") (pin "P55") (pinfunction "IO_L32P_4GCLK0_P55") (pintype "bidirectional"))
    )
    (net (code "152") (name "Net-(U1N-TCK)") (class "Default")
      (node (ref "R2") (pin "1") (pinfunction "1_1") (pintype "passive"))
      (node (ref "U1") (pin "P110") (pinfunction "TCK_P110") (pintype "bidirectional"))
    )
    (net (code "153") (name "Net-(U1N-TDI)") (class "Default")
      (node (ref "R1") (pin "1") (pinfunction "1_1") (pintype "passive"))
      (node (ref "U1") (pin "P144") (pinfunction "TDI_P144") (pintype "bidirectional"))
    )
    (net (code "154") (name "Net-(U1N-TMS)") (class "Default")
      (node (ref "R3") (pin "1") (pinfunction "1_1") (pintype "passive"))
      (node (ref "U1") (pin "P111") (pinfunction "TMS_P111") (pintype "bidirectional"))
    )
    (net (code "155") (name "unconnected-(IC1-NC.1-Pad2)") (class "Default")
      (node (ref "IC1") (pin "2") (pinfunction "NC.1_2") (pintype "bidirectional"))
    )
    (net (code "156") (name "unconnected-(IC1-NC.2-Pad9)") (class "Default")
      (node (ref "IC1") (pin "9") (pinfunction "NC.2_9") (pintype "bidirectional"))
    )
    (net (code "157") (name "unconnected-(IC1-NC.3-Pad12)") (class "Default")
      (node (ref "IC1") (pin "12") (pinfunction "NC.3_12") (pintype "bidirectional"))
    )
    (net (code "158") (name "unconnected-(IC1-NC.4-Pad14)") (class "Default")
      (node (ref "IC1") (pin "14") (pinfunction "NC.4_14") (pintype "bidirectional"))
    )
    (net (code "159") (name "unconnected-(IC1-NC.5-Pad15)") (class "Default")
      (node (ref "IC1") (pin "15") (pinfunction "NC.5_15") (pintype "bidirectional"))
    )
    (net (code "160") (name "unconnected-(IC1-NC.6-Pad16)") (class "Default")
      (node (ref "IC1") (pin "16") (pinfunction "NC.6_16") (pintype "bidirectional"))
    )
    (net (code "161") (name "unconnected-(IC1-{slash}CEO-Pad13)") (class "Default")
      (node (ref "IC1") (pin "13") (pinfunction "/CEO_13") (pintype "bidirectional"))
    )
    (net (code "162") (name "unconnected-(JP1-Pad3)") (class "Default")
      (node (ref "JP1") (pin "3") (pinfunction "3_3") (pintype "passive"))
    )
    (net (code "163") (name "unconnected-(JP1-Pad4)") (class "Default")
      (node (ref "JP1") (pin "4") (pinfunction "4_4") (pintype "passive"))
    )
    (net (code "164") (name "unconnected-(JP1-Pad5)") (class "Default")
      (node (ref "JP1") (pin "5") (pinfunction "5_5") (pintype "passive"))
    )
    (net (code "165") (name "unconnected-(JP1-Pad6)") (class "Default")
      (node (ref "JP1") (pin "6") (pinfunction "6_6") (pintype "passive"))
    )
    (net (code "166") (name "unconnected-(JP1-Pad7)") (class "Default")
      (node (ref "JP1") (pin "7") (pinfunction "7_7") (pintype "passive"))
    )
    (net (code "167") (name "unconnected-(JP1-Pad8)") (class "Default")
      (node (ref "JP1") (pin "8") (pinfunction "8_8") (pintype "passive"))
    )
    (net (code "168") (name "unconnected-(JP1-Pad9)") (class "Default")
      (node (ref "JP1") (pin "9") (pinfunction "9_9") (pintype "passive"))
    )
    (net (code "169") (name "unconnected-(JP1-Pad10)") (class "Default")
      (node (ref "JP1") (pin "10") (pinfunction "10_10") (pintype "passive"))
    )
    (net (code "170") (name "unconnected-(JP1-Pad11)") (class "Default")
      (node (ref "JP1") (pin "11") (pinfunction "11_11") (pintype "passive"))
    )
    (net (code "171") (name "unconnected-(JP1-Pad12)") (class "Default")
      (node (ref "JP1") (pin "12") (pinfunction "12_12") (pintype "passive"))
    )
    (net (code "172") (name "unconnected-(JP1-Pad13)") (class "Default")
      (node (ref "JP1") (pin "13") (pinfunction "13_13") (pintype "passive"))
    )
    (net (code "173") (name "unconnected-(JP1-Pad14)") (class "Default")
      (node (ref "JP1") (pin "14") (pinfunction "14_14") (pintype "passive"))
    )
    (net (code "174") (name "unconnected-(JP1-Pad15)") (class "Default")
      (node (ref "JP1") (pin "15") (pinfunction "15_15") (pintype "passive"))
    )
    (net (code "175") (name "unconnected-(JP1-Pad16)") (class "Default")
      (node (ref "JP1") (pin "16") (pinfunction "16_16") (pintype "passive"))
    )
    (net (code "176") (name "unconnected-(JP1-Pad17)") (class "Default")
      (node (ref "JP1") (pin "17") (pinfunction "17_17") (pintype "passive"))
    )
    (net (code "177") (name "unconnected-(JP1-Pad18)") (class "Default")
      (node (ref "JP1") (pin "18") (pinfunction "18_18") (pintype "passive"))
    )
    (net (code "178") (name "unconnected-(JP1-Pad19)") (class "Default")
      (node (ref "JP1") (pin "19") (pinfunction "19_19") (pintype "passive"))
    )
    (net (code "179") (name "unconnected-(JP1-Pad20)") (class "Default")
      (node (ref "JP1") (pin "20") (pinfunction "20_20") (pintype "passive"))
    )
    (net (code "180") (name "unconnected-(REG1.2-VOUT2-Pad2)") (class "Default")
      (node (ref "REG1.2") (pin "2") (pinfunction "VOUT2_2") (pintype "bidirectional"))
    )
    (net (code "181") (name "unconnected-(REG2.5-VOUT2-Pad2)") (class "Default")
      (node (ref "REG2.5") (pin "2") (pinfunction "VOUT2_2") (pintype "bidirectional"))
    )
    (net (code "182") (name "unconnected-(SJ1-Pad1)") (class "Default")
      (node (ref "SJ1") (pin "1") (pinfunction "1_1") (pintype "passive"))
    )
    (net (code "183") (name "unconnected-(SJ1-Pad2)") (class "Default")
      (node (ref "SJ1") (pin "2") (pinfunction "2_2") (pintype "passive"))
    )
    (net (code "184") (name "unconnected-(SJ2-Pad1)") (class "Default")
      (node (ref "SJ2") (pin "1") (pinfunction "1_1") (pintype "passive"))
    )
    (net (code "185") (name "unconnected-(SJ2-Pad2)") (class "Default")
      (node (ref "SJ2") (pin "2") (pinfunction "2_2") (pintype "passive"))
    )
    (net (code "186") (name "unconnected-(T4-B-Pad1)") (class "Default")
      (node (ref "T4") (pin "1") (pinfunction "B_1") (pintype "passive"))
    )
    (net (code "187") (name "unconnected-(T4-C-Pad3)") (class "Default")
      (node (ref "T4") (pin "3") (pinfunction "C_3") (pintype "passive"))
    )
    (net (code "188") (name "unconnected-(T4-E-Pad2)") (class "Default")
      (node (ref "T4") (pin "2") (pinfunction "E_2") (pintype "passive"))
    )
    (net (code "189") (name "unconnected-(U$2-TRI-PadENA)") (class "Default")
      (node (ref "U$2") (pin "ENA") (pinfunction "TRI_ENA") (pintype "input"))
    )
    (net (code "190") (name "unconnected-(U$4-VOUT2-Pad2)") (class "Default")
      (node (ref "U$4") (pin "2") (pinfunction "VOUT2_2") (pintype "bidirectional"))
    )
    (net (code "191") (name "unconnected-(U1F-IO-PadP76)") (class "Default")
      (node (ref "U1") (pin "P76") (pinfunction "IO_P76") (pintype "bidirectional"))
    )
    (net (code "192") (name "unconnected-(U1F-IO_L01N_3VRP_3-PadP74)") (class "Default")
      (node (ref "U1") (pin "P74") (pinfunction "IO_L01N_3VRP_3_P74") (pintype "bidirectional"))
    )
    (net (code "193") (name "unconnected-(U1F-IO_L01P_3VRN_3-PadP73)") (class "Default")
      (node (ref "U1") (pin "P73") (pinfunction "IO_L01P_3VRN_3_P73") (pintype "bidirectional"))
    )
    (net (code "194") (name "unconnected-(U1F-IO_L20N_3-PadP78)") (class "Default")
      (node (ref "U1") (pin "P78") (pinfunction "IO_L20N_3_P78") (pintype "bidirectional"))
    )
    (net (code "195") (name "unconnected-(U1F-IO_L20P_3-PadP77)") (class "Default")
      (node (ref "U1") (pin "P77") (pinfunction "IO_L20P_3_P77") (pintype "bidirectional"))
    )
    (net (code "196") (name "unconnected-(U1F-IO_L21N_3-PadP80)") (class "Default")
      (node (ref "U1") (pin "P80") (pinfunction "IO_L21N_3_P80") (pintype "bidirectional"))
    )
    (net (code "197") (name "unconnected-(U1F-IO_L21P_3-PadP79)") (class "Default")
      (node (ref "U1") (pin "P79") (pinfunction "IO_L21P_3_P79") (pintype "bidirectional"))
    )
    (net (code "198") (name "unconnected-(U1F-IO_L22N_3-PadP83)") (class "Default")
      (node (ref "U1") (pin "P83") (pinfunction "IO_L22N_3_P83") (pintype "bidirectional"))
    )
    (net (code "199") (name "unconnected-(U1F-IO_L22P_3-PadP82)") (class "Default")
      (node (ref "U1") (pin "P82") (pinfunction "IO_L22P_3_P82") (pintype "bidirectional"))
    )
    (net (code "200") (name "unconnected-(U1F-IO_L23N_3-PadP85)") (class "Default")
      (node (ref "U1") (pin "P85") (pinfunction "IO_L23N_3_P85") (pintype "bidirectional"))
    )
    (net (code "201") (name "unconnected-(U1F-IO_L23P_3VREF_3-PadP84)") (class "Default")
      (node (ref "U1") (pin "P84") (pinfunction "IO_L23P_3VREF_3_P84") (pintype "bidirectional"))
    )
    (net (code "202") (name "unconnected-(U1F-IO_L24N_3-PadP87)") (class "Default")
      (node (ref "U1") (pin "P87") (pinfunction "IO_L24N_3_P87") (pintype "bidirectional"))
    )
    (net (code "203") (name "unconnected-(U1F-IO_L24P_3-PadP86)") (class "Default")
      (node (ref "U1") (pin "P86") (pinfunction "IO_L24P_3_P86") (pintype "bidirectional"))
    )
    (net (code "204") (name "unconnected-(U1F-IO_L40N_3VREF_3-PadP90)") (class "Default")
      (node (ref "U1") (pin "P90") (pinfunction "IO_L40N_3VREF_3_P90") (pintype "bidirectional"))
    )
    (net (code "205") (name "unconnected-(U1F-IO_L40P_3-PadP89)") (class "Default")
      (node (ref "U1") (pin "P89") (pinfunction "IO_L40P_3_P89") (pintype "bidirectional"))
    )
    (net (code "206") (name "unconnected-(U1G-IO_L31P_4DOUTBUSY-PadP57)") (class "Default")
      (node (ref "U1") (pin "P57") (pinfunction "IO_L31P_4DOUTBUSY_P57") (pintype "bidirectional"))
    )
    (net (code "207") (name "unconnected-(U1N-HSWAP_EN-PadP142)") (class "Default")
      (node (ref "U1") (pin "P142") (pinfunction "HSWAP_EN_P142") (pintype "bidirectional"))
    )
    (net (code "208") (name "unconnected-(X1-Pad10)") (class "Default")
      (node (ref "X1") (pin "10") (pinfunction "10_10") (pintype "passive"))
    )
    (net (code "209") (name "unconnected-(X1-Pad12)") (class "Default")
      (node (ref "X1") (pin "12") (pinfunction "12_12") (pintype "passive"))
    )
    (net (code "210") (name "unconnected-(X3-Pad2)") (class "Default")
      (node (ref "X3") (pin "2") (pinfunction "2_2") (pintype "passive"))
    )
    (net (code "211") (name "unconnected-(X3-Pad8)") (class "Default")
      (node (ref "X3") (pin "8") (pinfunction "8_8") (pintype "passive"))
    )
    (net (code "212") (name "unconnected-(X4-PadG2)") (class "Default")
      (node (ref "X4") (pin "G2") (pinfunction "G2_G2") (pintype "passive"))
    )
    (net (code "213") (name "unconnected-(X5-PadG2)") (class "Default")
      (node (ref "X5") (pin "G2") (pinfunction "G2_G2") (pintype "passive"))
    )
    (net (code "214") (name "unconnected-(X6-Pad1)") (class "Default")
      (node (ref "X6") (pin "1") (pinfunction "1_1") (pintype "passive"))
    )
  )
)
